# Sobel_FPGA_Block_1.net
KiCad netlist of a schematic drawn in Altium Designer
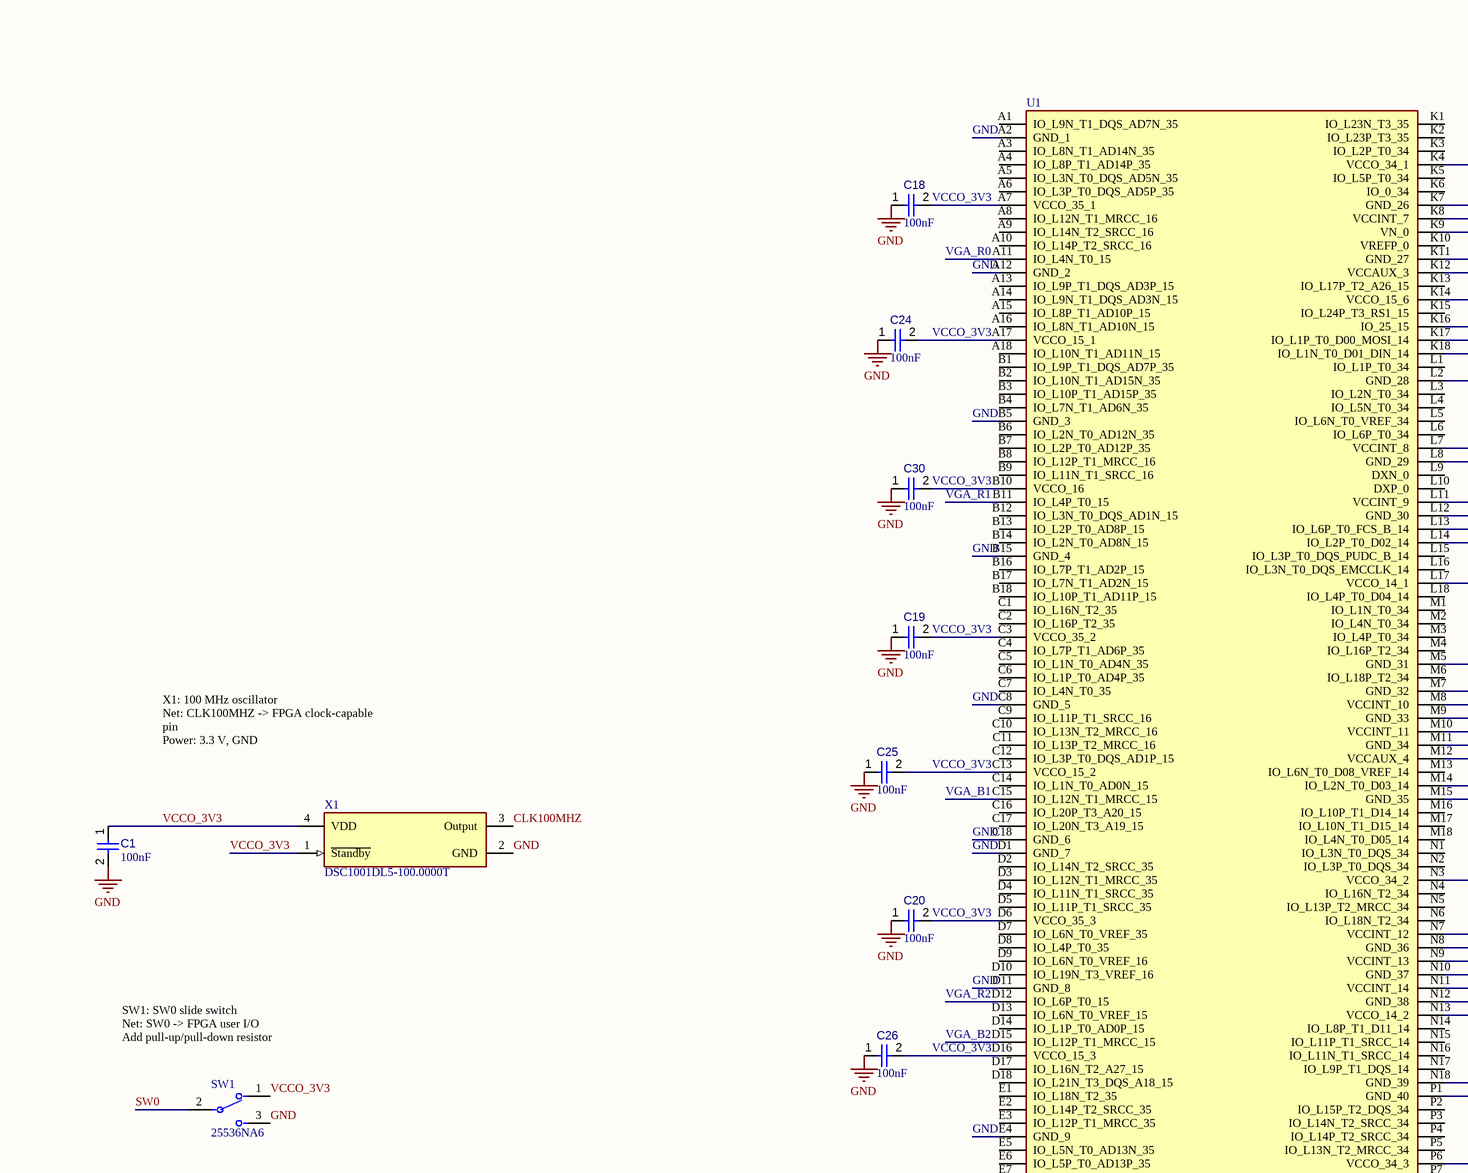
[diagram p0: Sobel_FPGA_Block (1).SchDoc, top left]
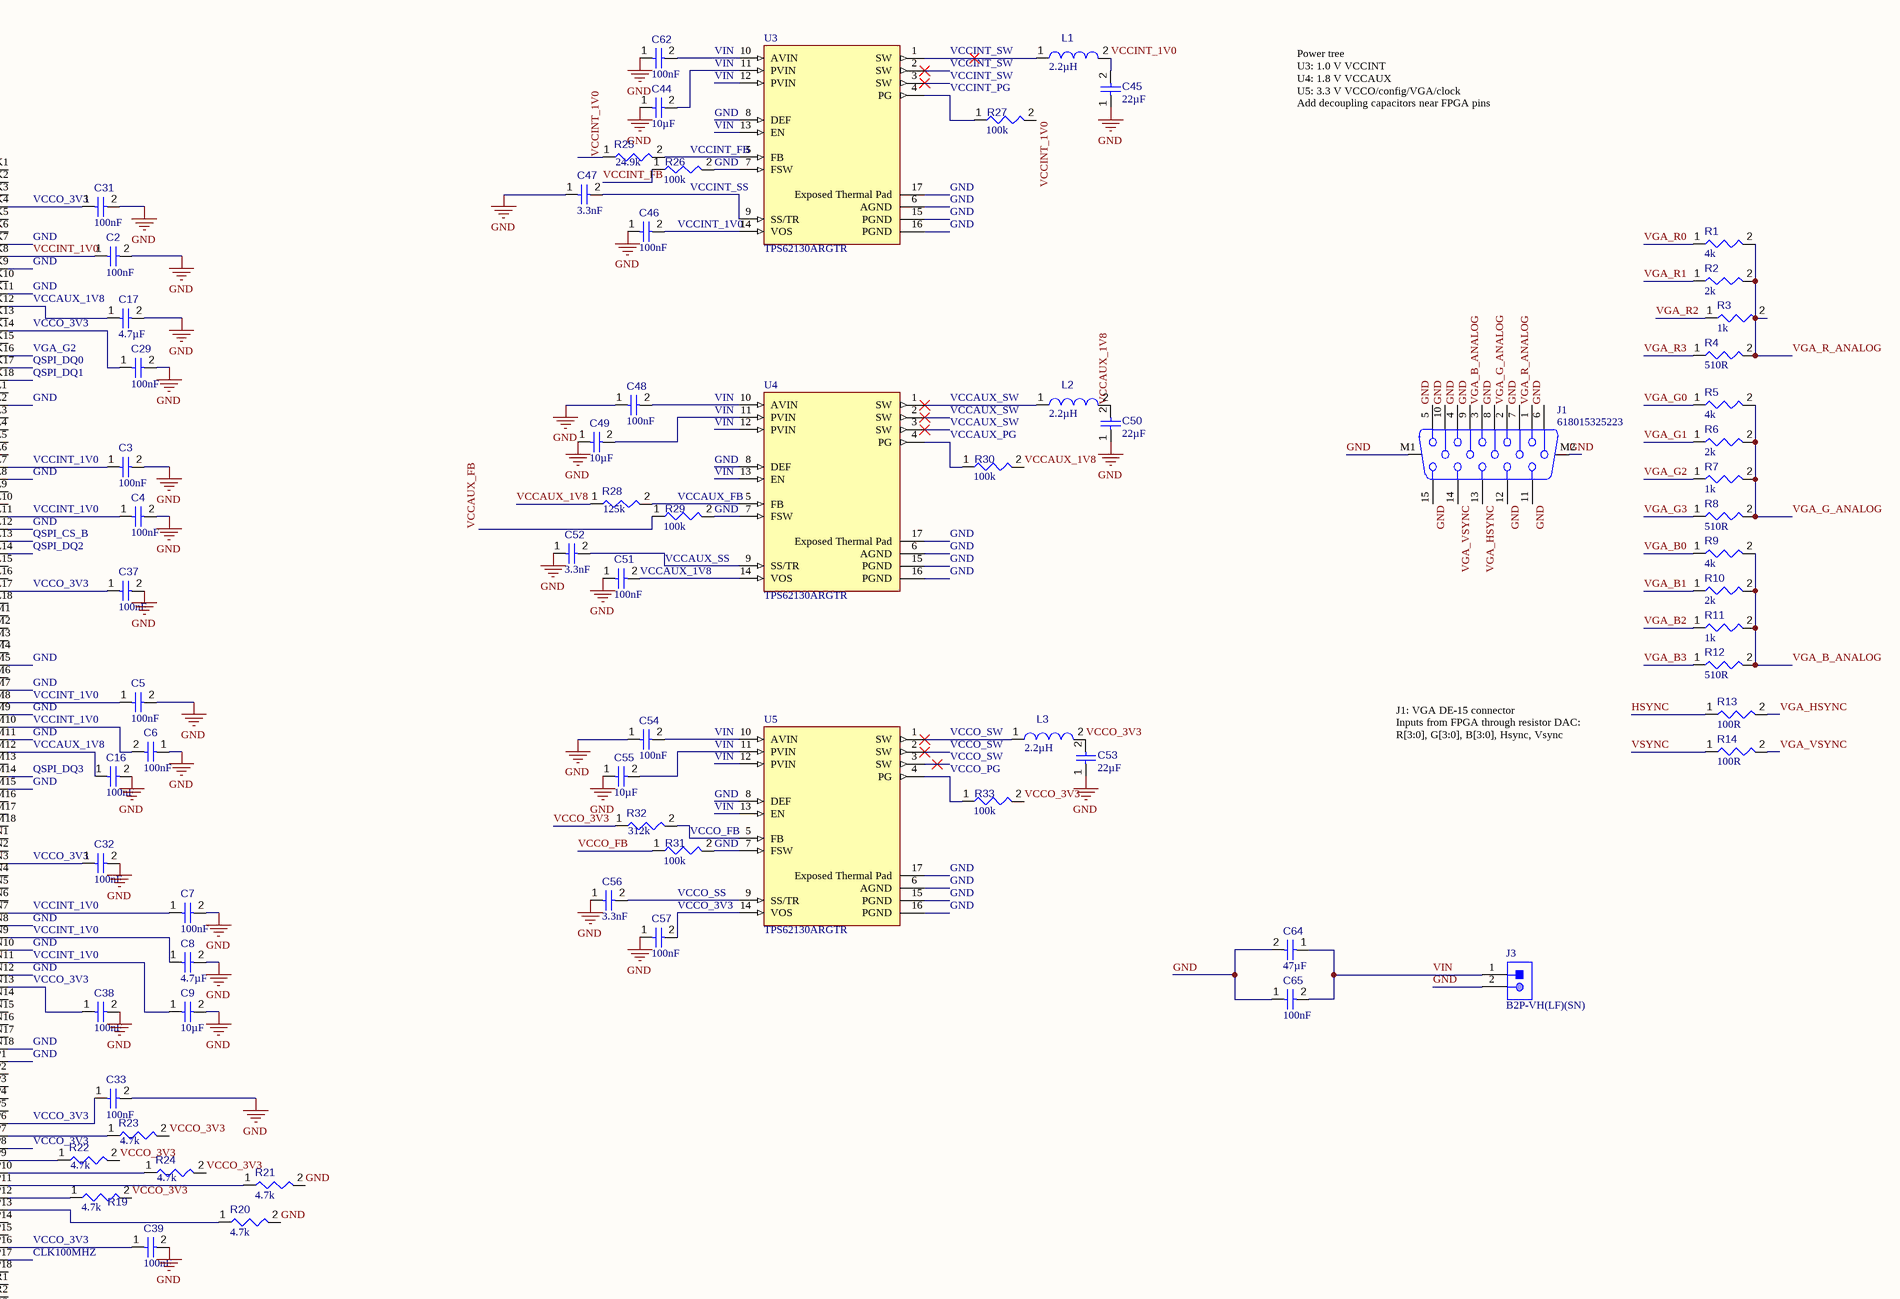
[diagram p1: Sobel_FPGA_Block (1).SchDoc, top right]
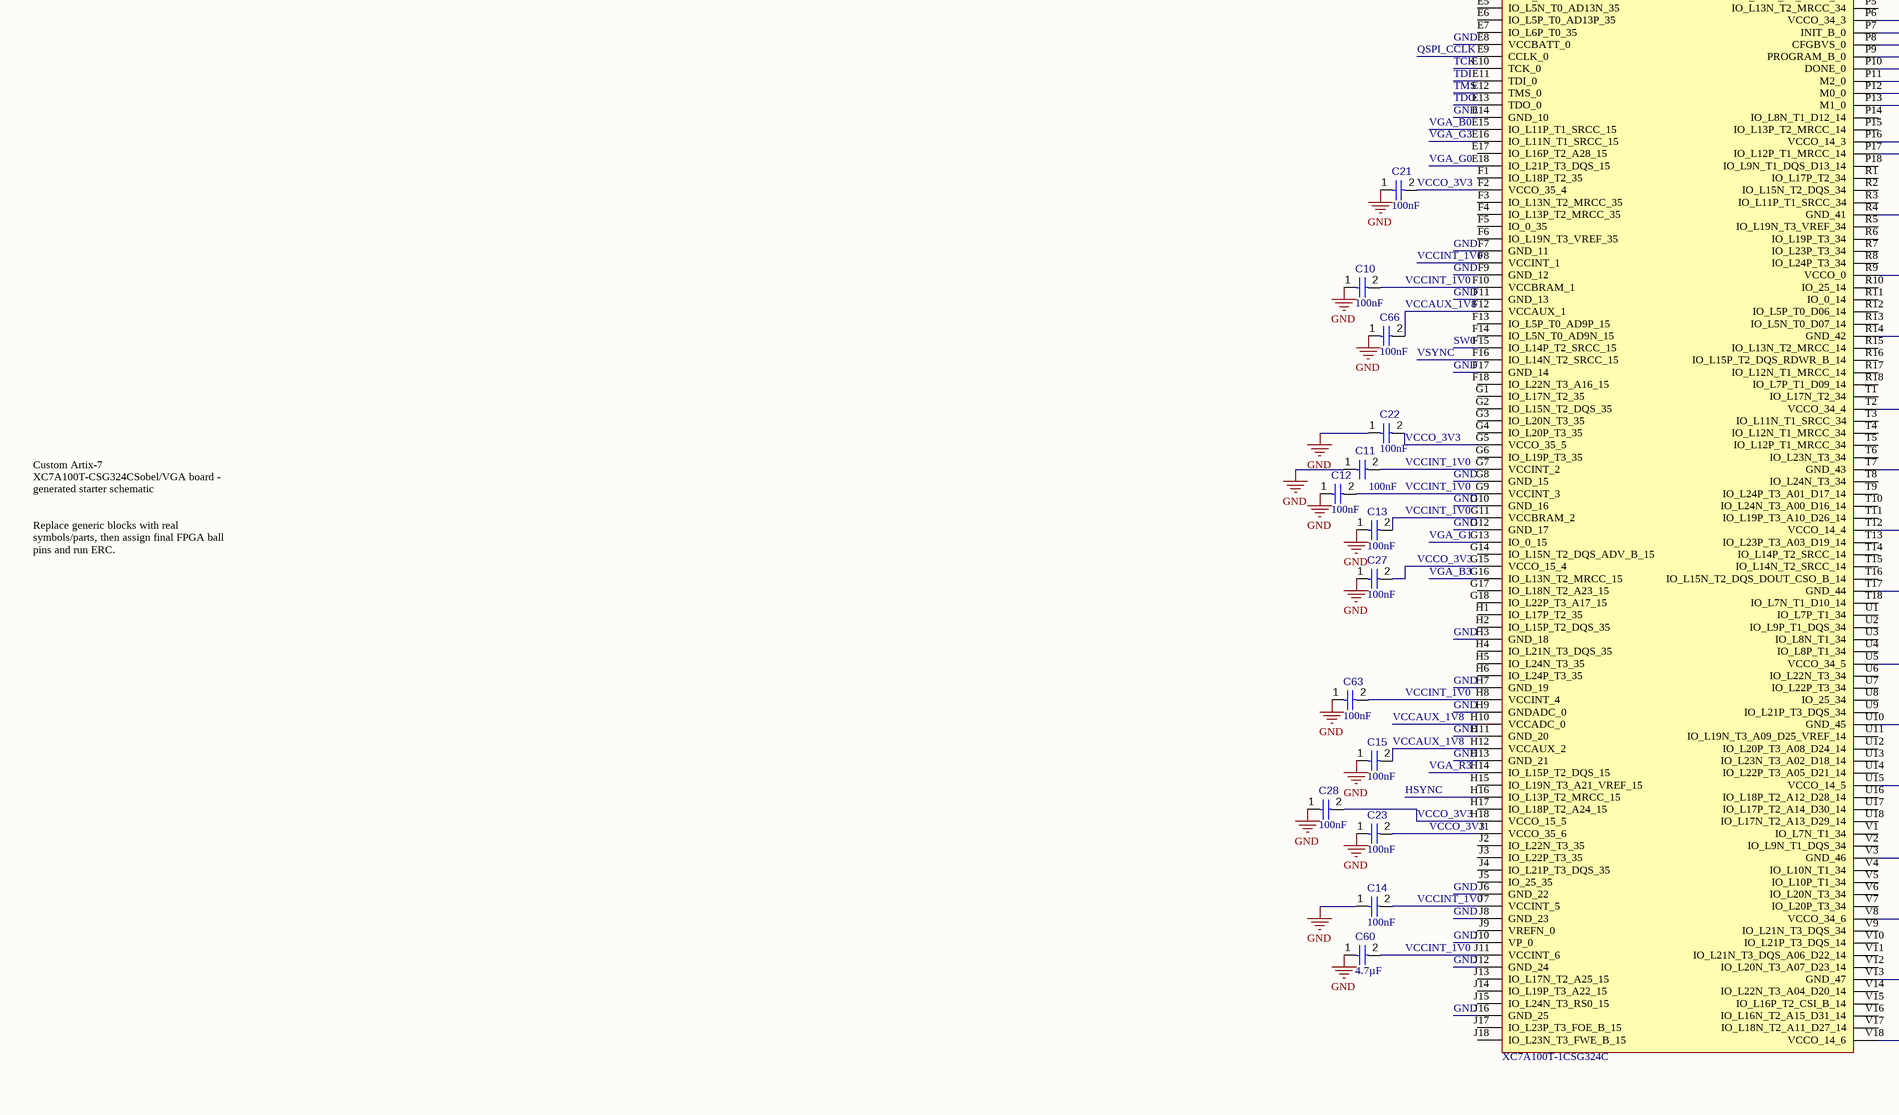
[diagram p2: Sobel_FPGA_Block (1).SchDoc, bottom left]
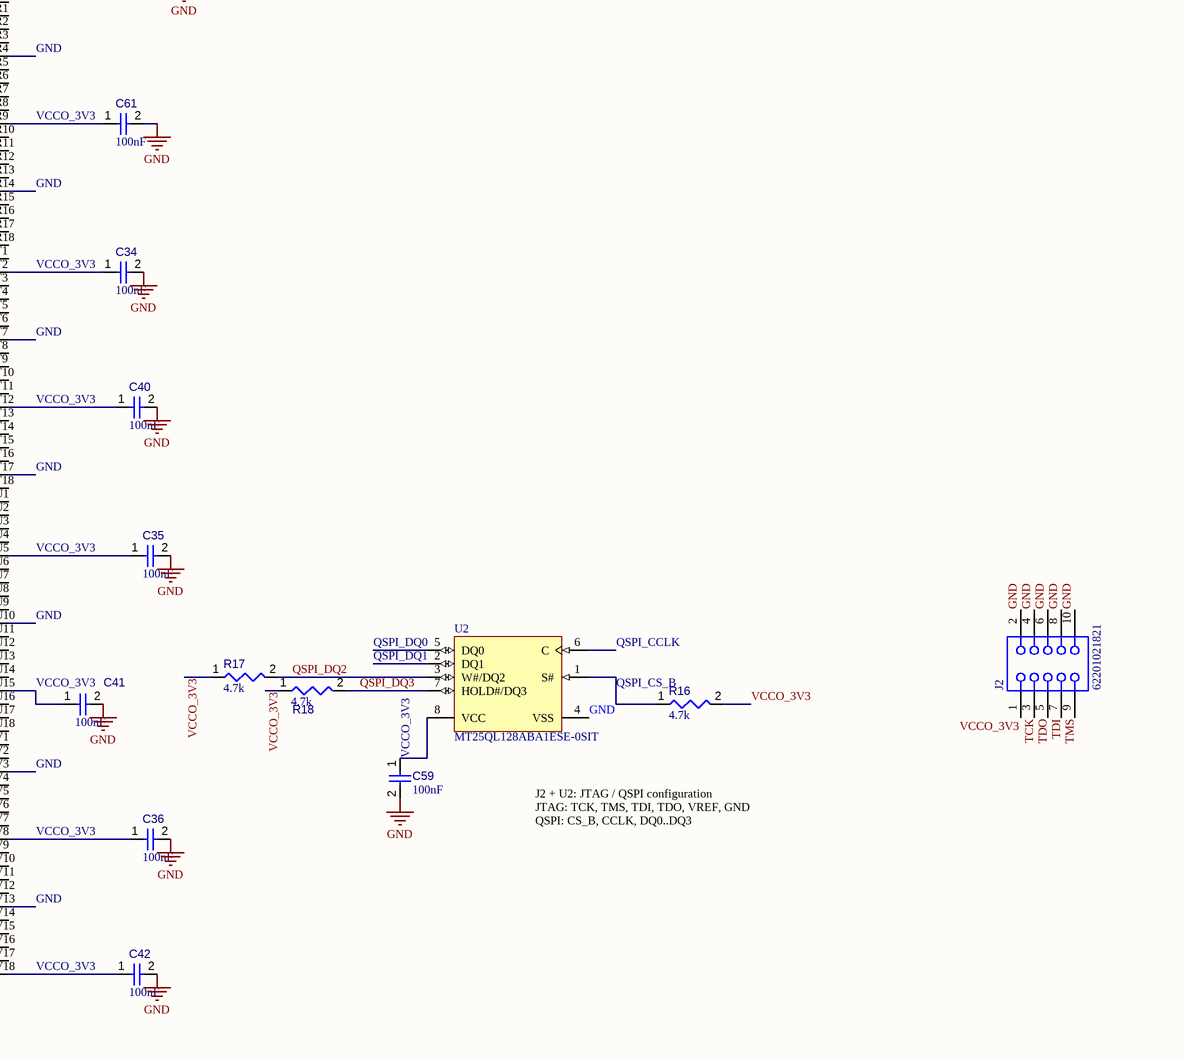
[diagram p3: Sobel_FPGA_Block (1).SchDoc, bottom right]

(export (version "E")
  (design (tool "Eeschema 10.0.6"))
  (components
    (comp (ref "C1")
      (value "100nF")
      (footprint "CAPC1005X56X25NL10T15")
      (description "Chip Capacitor, 6.8 nF, +/- 10%, 16 V, 0402 (1005 Metric)")
      (fields (field (name "TOLERANCE") "10%") (field (name "Comment") "Capacitor 6.8 nF +/- 10% 16 V 0402"))
      (libsource (lib "Turja Barua") (part "CAP-NP-2"))
    )
    (comp (ref "C2")
      (value "100nF")
      (footprint "CAPC1005X56X25NL10T15")
      (description "Chip Capacitor, 6.8 nF, +/- 10%, 16 V, 0402 (1005 Metric)")
      (fields (field (name "TOLERANCE") "10%") (field (name "Comment") "Capacitor 6.8 nF +/- 10% 16 V 0402"))
      (libsource (lib "Turja Barua") (part "CAP-NP-2"))
    )
    (comp (ref "C3")
      (value "100nF")
      (footprint "CAPC1005X56X25NL10T15")
      (description "Chip Capacitor, 6.8 nF, +/- 10%, 16 V, 0402 (1005 Metric)")
      (fields (field (name "TOLERANCE") "10%") (field (name "Comment") "Capacitor 6.8 nF +/- 10% 16 V 0402"))
      (libsource (lib "Turja Barua") (part "CAP-NP-2"))
    )
    (comp (ref "C4")
      (value "100nF")
      (footprint "CAPC1005X56X25NL10T15")
      (description "Chip Capacitor, 6.8 nF, +/- 10%, 16 V, 0402 (1005 Metric)")
      (fields (field (name "TOLERANCE") "10%") (field (name "Comment") "Capacitor 6.8 nF +/- 10% 16 V 0402"))
      (libsource (lib "Turja Barua") (part "CAP-NP-2"))
    )
    (comp (ref "C5")
      (value "100nF")
      (footprint "CAPC1005X56X25NL10T15")
      (description "Chip Capacitor, 6.8 nF, +/- 10%, 16 V, 0402 (1005 Metric)")
      (fields (field (name "TOLERANCE") "10%") (field (name "Comment") "Capacitor 6.8 nF +/- 10% 16 V 0402"))
      (libsource (lib "Turja Barua") (part "CAP-NP-2"))
    )
    (comp (ref "C6")
      (value "100nF")
      (footprint "CAPC1005X56X25NL10T15")
      (description "Chip Capacitor, 6.8 nF, +/- 10%, 16 V, 0402 (1005 Metric)")
      (fields (field (name "TOLERANCE") "10%") (field (name "Comment") "Capacitor 6.8 nF +/- 10% 16 V 0402"))
      (libsource (lib "Turja Barua") (part "CAP-NP-2"))
    )
    (comp (ref "C7")
      (value "100nF")
      (footprint "CAPC1005X56X25NL10T15")
      (description "Chip Capacitor, 6.8 nF, +/- 10%, 16 V, 0402 (1005 Metric)")
      (fields (field (name "TOLERANCE") "10%") (field (name "Comment") "Capacitor 6.8 nF +/- 10% 16 V 0402"))
      (libsource (lib "Turja Barua") (part "CAP-NP-2"))
    )
    (comp (ref "C8")
      (value "4.7µF")
      (footprint "CAPC3216X180X50NL20T25")
      (description "Chip Capacitor, 10 uF, +/- 10%, 16 V, 1206 (3216 Metric)")
      (fields (field (name "TOLERANCE") "10%") (field (name "Comment") "Capacitor 10 uF +/- 10% 16 V 1206"))
      (libsource (lib "Turja Barua") (part "CAP-NP-2"))
    )
    (comp (ref "C9")
      (value "10µF")
      (footprint "CAPC3216X180X50NL20T25")
      (description "Chip Capacitor, 10 uF, +/- 10%, 16 V, 1206 (3216 Metric)")
      (fields (field (name "TOLERANCE") "10%") (field (name "Comment") "Capacitor 10 uF +/- 10% 16 V 1206"))
      (libsource (lib "Turja Barua") (part "CAP-NP-2"))
    )
    (comp (ref "C10")
      (value "100nF")
      (footprint "CAPC1005X56X25NL10T15")
      (description "Chip Capacitor, 6.8 nF, +/- 10%, 16 V, 0402 (1005 Metric)")
      (fields (field (name "TOLERANCE") "10%") (field (name "Comment") "Capacitor 6.8 nF +/- 10% 16 V 0402"))
      (libsource (lib "Turja Barua") (part "CAP-NP-2"))
    )
    (comp (ref "C11")
      (value "100nF")
      (footprint "CAPC1005X56X25NL10T15")
      (description "Chip Capacitor, 6.8 nF, +/- 10%, 16 V, 0402 (1005 Metric)")
      (fields (field (name "TOLERANCE") "10%") (field (name "Comment") "Capacitor 6.8 nF +/- 10% 16 V 0402"))
      (libsource (lib "Turja Barua") (part "CAP-NP-2"))
    )
    (comp (ref "C12")
      (value "100nF")
      (footprint "CAPC1005X56X25NL10T15")
      (description "Chip Capacitor, 6.8 nF, +/- 10%, 16 V, 0402 (1005 Metric)")
      (fields (field (name "TOLERANCE") "10%") (field (name "Comment") "Capacitor 6.8 nF +/- 10% 16 V 0402"))
      (libsource (lib "Turja Barua") (part "CAP-NP-2"))
    )
    (comp (ref "C13")
      (value "100nF")
      (footprint "CAPC1005X56X25NL10T15")
      (description "Chip Capacitor, 6.8 nF, +/- 10%, 16 V, 0402 (1005 Metric)")
      (fields (field (name "TOLERANCE") "10%") (field (name "Comment") "Capacitor 6.8 nF +/- 10% 16 V 0402"))
      (libsource (lib "Turja Barua") (part "CAP-NP-2"))
    )
    (comp (ref "C14")
      (value "100nF")
      (footprint "CAPC1005X56X25NL10T15")
      (description "Chip Capacitor, 6.8 nF, +/- 10%, 16 V, 0402 (1005 Metric)")
      (fields (field (name "TOLERANCE") "10%") (field (name "Comment") "Capacitor 6.8 nF +/- 10% 16 V 0402"))
      (libsource (lib "Turja Barua") (part "CAP-NP-2"))
    )
    (comp (ref "C15")
      (value "100nF")
      (footprint "CAPC1005X56X25NL10T15")
      (description "Chip Capacitor, 6.8 nF, +/- 10%, 16 V, 0402 (1005 Metric)")
      (fields (field (name "TOLERANCE") "10%") (field (name "Comment") "Capacitor 6.8 nF +/- 10% 16 V 0402"))
      (libsource (lib "Turja Barua") (part "CAP-NP-2"))
    )
    (comp (ref "C16")
      (value "100nF")
      (footprint "CAPC1005X56X25NL10T15")
      (description "Chip Capacitor, 6.8 nF, +/- 10%, 16 V, 0402 (1005 Metric)")
      (fields (field (name "TOLERANCE") "10%") (field (name "Comment") "Capacitor 6.8 nF +/- 10% 16 V 0402"))
      (libsource (lib "Turja Barua") (part "CAP-NP-2"))
    )
    (comp (ref "C17")
      (value "4.7µF")
      (footprint "CAPC3216X180X50NL20T25")
      (description "Chip Capacitor, 10 uF, +/- 10%, 16 V, 1206 (3216 Metric)")
      (fields (field (name "TOLERANCE") "10%") (field (name "Comment") "Capacitor 10 uF +/- 10% 16 V 1206"))
      (libsource (lib "Turja Barua") (part "CAP-NP-2"))
    )
    (comp (ref "C18")
      (value "100nF")
      (footprint "CAPC1005X56X25NL10T15")
      (description "Chip Capacitor, 6.8 nF, +/- 10%, 16 V, 0402 (1005 Metric)")
      (fields (field (name "TOLERANCE") "10%") (field (name "Comment") "Capacitor 6.8 nF +/- 10% 16 V 0402"))
      (libsource (lib "Turja Barua") (part "CAP-NP-2"))
    )
    (comp (ref "C19")
      (value "100nF")
      (footprint "CAPC1005X56X25NL10T15")
      (description "Chip Capacitor, 6.8 nF, +/- 10%, 16 V, 0402 (1005 Metric)")
      (fields (field (name "TOLERANCE") "10%") (field (name "Comment") "Capacitor 6.8 nF +/- 10% 16 V 0402"))
      (libsource (lib "Turja Barua") (part "CAP-NP-2"))
    )
    (comp (ref "C20")
      (value "100nF")
      (footprint "CAPC1005X56X25NL10T15")
      (description "Chip Capacitor, 6.8 nF, +/- 10%, 16 V, 0402 (1005 Metric)")
      (fields (field (name "TOLERANCE") "10%") (field (name "Comment") "Capacitor 6.8 nF +/- 10% 16 V 0402"))
      (libsource (lib "Turja Barua") (part "CAP-NP-2"))
    )
    (comp (ref "C21")
      (value "100nF")
      (footprint "CAPC1005X56X25NL10T15")
      (description "Chip Capacitor, 6.8 nF, +/- 10%, 16 V, 0402 (1005 Metric)")
      (fields (field (name "TOLERANCE") "10%") (field (name "Comment") "Capacitor 6.8 nF +/- 10% 16 V 0402"))
      (libsource (lib "Turja Barua") (part "CAP-NP-2"))
    )
    (comp (ref "C22")
      (value "100nF")
      (footprint "CAPC1005X56X25NL10T15")
      (description "Chip Capacitor, 6.8 nF, +/- 10%, 16 V, 0402 (1005 Metric)")
      (fields (field (name "TOLERANCE") "10%") (field (name "Comment") "Capacitor 6.8 nF +/- 10% 16 V 0402"))
      (libsource (lib "Turja Barua") (part "CAP-NP-2"))
    )
    (comp (ref "C23")
      (value "100nF")
      (footprint "CAPC1005X56X25NL10T15")
      (description "Chip Capacitor, 6.8 nF, +/- 10%, 16 V, 0402 (1005 Metric)")
      (fields (field (name "TOLERANCE") "10%") (field (name "Comment") "Capacitor 6.8 nF +/- 10% 16 V 0402"))
      (libsource (lib "Turja Barua") (part "CAP-NP-2"))
    )
    (comp (ref "C24")
      (value "100nF")
      (footprint "CAPC1005X56X25NL10T15")
      (description "Chip Capacitor, 6.8 nF, +/- 10%, 16 V, 0402 (1005 Metric)")
      (fields (field (name "TOLERANCE") "10%") (field (name "Comment") "Capacitor 6.8 nF +/- 10% 16 V 0402"))
      (libsource (lib "Turja Barua") (part "CAP-NP-2"))
    )
    (comp (ref "C25")
      (value "100nF")
      (footprint "CAPC1005X56X25NL10T15")
      (description "Chip Capacitor, 6.8 nF, +/- 10%, 16 V, 0402 (1005 Metric)")
      (fields (field (name "TOLERANCE") "10%") (field (name "Comment") "Capacitor 6.8 nF +/- 10% 16 V 0402"))
      (libsource (lib "Turja Barua") (part "CAP-NP-2"))
    )
    (comp (ref "C26")
      (value "100nF")
      (footprint "CAPC1005X56X25NL10T15")
      (description "Chip Capacitor, 6.8 nF, +/- 10%, 16 V, 0402 (1005 Metric)")
      (fields (field (name "TOLERANCE") "10%") (field (name "Comment") "Capacitor 6.8 nF +/- 10% 16 V 0402"))
      (libsource (lib "Turja Barua") (part "CAP-NP-2"))
    )
    (comp (ref "C27")
      (value "100nF")
      (footprint "CAPC1005X56X25NL10T15")
      (description "Chip Capacitor, 6.8 nF, +/- 10%, 16 V, 0402 (1005 Metric)")
      (fields (field (name "TOLERANCE") "10%") (field (name "Comment") "Capacitor 6.8 nF +/- 10% 16 V 0402"))
      (libsource (lib "Turja Barua") (part "CAP-NP-2"))
    )
    (comp (ref "C28")
      (value "100nF")
      (footprint "CAPC1005X56X25NL10T15")
      (description "Chip Capacitor, 6.8 nF, +/- 10%, 16 V, 0402 (1005 Metric)")
      (fields (field (name "TOLERANCE") "10%") (field (name "Comment") "Capacitor 6.8 nF +/- 10% 16 V 0402"))
      (libsource (lib "Turja Barua") (part "CAP-NP-2"))
    )
    (comp (ref "C29")
      (value "100nF")
      (footprint "CAPC1005X56X25NL10T15")
      (description "Chip Capacitor, 6.8 nF, +/- 10%, 16 V, 0402 (1005 Metric)")
      (fields (field (name "TOLERANCE") "10%") (field (name "Comment") "Capacitor 6.8 nF +/- 10% 16 V 0402"))
      (libsource (lib "Turja Barua") (part "CAP-NP-2"))
    )
    (comp (ref "C30")
      (value "100nF")
      (footprint "CAPC1005X56X25NL10T15")
      (description "Chip Capacitor, 6.8 nF, +/- 10%, 16 V, 0402 (1005 Metric)")
      (fields (field (name "TOLERANCE") "10%") (field (name "Comment") "Capacitor 6.8 nF +/- 10% 16 V 0402"))
      (libsource (lib "Turja Barua") (part "CAP-NP-2"))
    )
    (comp (ref "C31")
      (value "100nF")
      (footprint "CAPC1005X56X25NL10T15")
      (description "Chip Capacitor, 6.8 nF, +/- 10%, 16 V, 0402 (1005 Metric)")
      (fields (field (name "TOLERANCE") "10%") (field (name "Comment") "Capacitor 6.8 nF +/- 10% 16 V 0402"))
      (libsource (lib "Turja Barua") (part "CAP-NP-2"))
    )
    (comp (ref "C32")
      (value "100nF")
      (footprint "CAPC1005X56X25NL10T15")
      (description "Chip Capacitor, 6.8 nF, +/- 10%, 16 V, 0402 (1005 Metric)")
      (fields (field (name "TOLERANCE") "10%") (field (name "Comment") "Capacitor 6.8 nF +/- 10% 16 V 0402"))
      (libsource (lib "Turja Barua") (part "CAP-NP-2"))
    )
    (comp (ref "C33")
      (value "100nF")
      (footprint "CAPC1005X56X25NL10T15")
      (description "Chip Capacitor, 6.8 nF, +/- 10%, 16 V, 0402 (1005 Metric)")
      (fields (field (name "TOLERANCE") "10%") (field (name "Comment") "Capacitor 6.8 nF +/- 10% 16 V 0402"))
      (libsource (lib "Turja Barua") (part "CAP-NP-2"))
    )
    (comp (ref "C34")
      (value "100nF")
      (footprint "CAPC1005X56X25NL10T15")
      (description "Chip Capacitor, 6.8 nF, +/- 10%, 16 V, 0402 (1005 Metric)")
      (fields (field (name "TOLERANCE") "10%") (field (name "Comment") "Capacitor 6.8 nF +/- 10% 16 V 0402"))
      (libsource (lib "Turja Barua") (part "CAP-NP-2"))
    )
    (comp (ref "C35")
      (value "100nF")
      (footprint "CAPC1005X56X25NL10T15")
      (description "Chip Capacitor, 6.8 nF, +/- 10%, 16 V, 0402 (1005 Metric)")
      (fields (field (name "TOLERANCE") "10%") (field (name "Comment") "Capacitor 6.8 nF +/- 10% 16 V 0402"))
      (libsource (lib "Turja Barua") (part "CAP-NP-2"))
    )
    (comp (ref "C36")
      (value "100nF")
      (footprint "CAPC1005X56X25NL10T15")
      (description "Chip Capacitor, 6.8 nF, +/- 10%, 16 V, 0402 (1005 Metric)")
      (fields (field (name "TOLERANCE") "10%") (field (name "Comment") "Capacitor 6.8 nF +/- 10% 16 V 0402"))
      (libsource (lib "Turja Barua") (part "CAP-NP-2"))
    )
    (comp (ref "C37")
      (value "100nF")
      (footprint "CAPC1005X56X25NL10T15")
      (description "Chip Capacitor, 6.8 nF, +/- 10%, 16 V, 0402 (1005 Metric)")
      (fields (field (name "TOLERANCE") "10%") (field (name "Comment") "Capacitor 6.8 nF +/- 10% 16 V 0402"))
      (libsource (lib "Turja Barua") (part "CAP-NP-2"))
    )
    (comp (ref "C38")
      (value "100nF")
      (footprint "CAPC1005X56X25NL10T15")
      (description "Chip Capacitor, 6.8 nF, +/- 10%, 16 V, 0402 (1005 Metric)")
      (fields (field (name "TOLERANCE") "10%") (field (name "Comment") "Capacitor 6.8 nF +/- 10% 16 V 0402"))
      (libsource (lib "Turja Barua") (part "CAP-NP-2"))
    )
    (comp (ref "C39")
      (value "100nF")
      (footprint "CAPC1005X56X25NL10T15")
      (description "Chip Capacitor, 6.8 nF, +/- 10%, 16 V, 0402 (1005 Metric)")
      (fields (field (name "TOLERANCE") "10%") (field (name "Comment") "Capacitor 6.8 nF +/- 10% 16 V 0402"))
      (libsource (lib "Turja Barua") (part "CAP-NP-2"))
    )
    (comp (ref "C40")
      (value "100nF")
      (footprint "CAPC1005X56X25NL10T15")
      (description "Chip Capacitor, 6.8 nF, +/- 10%, 16 V, 0402 (1005 Metric)")
      (fields (field (name "TOLERANCE") "10%") (field (name "Comment") "Capacitor 6.8 nF +/- 10% 16 V 0402"))
      (libsource (lib "Turja Barua") (part "CAP-NP-2"))
    )
    (comp (ref "C41")
      (value "100nF")
      (footprint "CAPC1005X56X25NL10T15")
      (description "Chip Capacitor, 6.8 nF, +/- 10%, 16 V, 0402 (1005 Metric)")
      (fields (field (name "TOLERANCE") "10%") (field (name "Comment") "Capacitor 6.8 nF +/- 10% 16 V 0402"))
      (libsource (lib "Turja Barua") (part "CAP-NP-2"))
    )
    (comp (ref "C42")
      (value "100nF")
      (footprint "CAPC1005X56X25NL10T15")
      (description "Chip Capacitor, 6.8 nF, +/- 10%, 16 V, 0402 (1005 Metric)")
      (fields (field (name "TOLERANCE") "10%") (field (name "Comment") "Capacitor 6.8 nF +/- 10% 16 V 0402"))
      (libsource (lib "Turja Barua") (part "CAP-NP-2"))
    )
    (comp (ref "C44")
      (value "10µF")
      (footprint "CAPC3216X180X50NL20T25")
      (description "Chip Capacitor, 10 uF, +/- 10%, 16 V, 1206 (3216 Metric)")
      (fields (field (name "TOLERANCE") "10%") (field (name "Comment") "Capacitor 10 uF +/- 10% 16 V 1206"))
      (libsource (lib "Turja Barua") (part "CAP-NP-2"))
    )
    (comp (ref "C45")
      (value "22µF")
      (footprint "CAPC3216X180X50NL20T25")
      (description "Chip Capacitor, 10 uF, +/- 10%, 16 V, 1206 (3216 Metric)")
      (fields (field (name "TOLERANCE") "10%") (field (name "Comment") "Capacitor 10 uF +/- 10% 16 V 1206"))
      (libsource (lib "Turja Barua") (part "CAP-NP-2"))
    )
    (comp (ref "C46")
      (value "100nF")
      (footprint "CAPC1005X56X25NL10T15")
      (description "Chip Capacitor, 6.8 nF, +/- 10%, 16 V, 0402 (1005 Metric)")
      (fields (field (name "TOLERANCE") "10%") (field (name "Comment") "Capacitor 6.8 nF +/- 10% 16 V 0402"))
      (libsource (lib "Turja Barua") (part "CAP-NP-2"))
    )
    (comp (ref "C47")
      (value "3.3nF")
      (footprint "CAPC1005X56X25NL10T15")
      (description "Chip Capacitor, 6.8 nF, +/- 10%, 16 V, 0402 (1005 Metric)")
      (fields (field (name "TOLERANCE") "10%") (field (name "Comment") "Capacitor 6.8 nF +/- 10% 16 V 0402"))
      (libsource (lib "Turja Barua") (part "CAP-NP-2"))
    )
    (comp (ref "C48")
      (value "100nF")
      (footprint "CAPC1005X56X25NL10T15")
      (description "Chip Capacitor, 6.8 nF, +/- 10%, 16 V, 0402 (1005 Metric)")
      (fields (field (name "TOLERANCE") "10%") (field (name "Comment") "Capacitor 6.8 nF +/- 10% 16 V 0402"))
      (libsource (lib "Turja Barua") (part "CAP-NP-2"))
    )
    (comp (ref "C49")
      (value "10µF")
      (footprint "CAPC3216X180X50NL20T25")
      (description "Chip Capacitor, 10 uF, +/- 10%, 16 V, 1206 (3216 Metric)")
      (fields (field (name "TOLERANCE") "10%") (field (name "Comment") "Capacitor 10 uF +/- 10% 16 V 1206"))
      (libsource (lib "Turja Barua") (part "CAP-NP-2"))
    )
    (comp (ref "C50")
      (value "22µF")
      (footprint "CAPC3216X180X50NL20T25")
      (description "Chip Capacitor, 10 uF, +/- 10%, 16 V, 1206 (3216 Metric)")
      (fields (field (name "TOLERANCE") "10%") (field (name "Comment") "Capacitor 10 uF +/- 10% 16 V 1206"))
      (libsource (lib "Turja Barua") (part "CAP-NP-2"))
    )
    (comp (ref "C51")
      (value "100nF")
      (footprint "CAPC1005X56X25NL10T15")
      (description "Chip Capacitor, 6.8 nF, +/- 10%, 16 V, 0402 (1005 Metric)")
      (fields (field (name "TOLERANCE") "10%") (field (name "Comment") "Capacitor 6.8 nF +/- 10% 16 V 0402"))
      (libsource (lib "Turja Barua") (part "CAP-NP-2"))
    )
    (comp (ref "C52")
      (value "3.3nF")
      (footprint "CAPC1005X56X25NL10T15")
      (description "Chip Capacitor, 6.8 nF, +/- 10%, 16 V, 0402 (1005 Metric)")
      (fields (field (name "TOLERANCE") "10%") (field (name "Comment") "Capacitor 6.8 nF +/- 10% 16 V 0402"))
      (libsource (lib "Turja Barua") (part "CAP-NP-2"))
    )
    (comp (ref "C53")
      (value "22µF")
      (footprint "CAPC3216X180X50NL20T25")
      (description "Chip Capacitor, 10 uF, +/- 10%, 16 V, 1206 (3216 Metric)")
      (fields (field (name "TOLERANCE") "10%") (field (name "Comment") "Capacitor 10 uF +/- 10% 16 V 1206"))
      (libsource (lib "Turja Barua") (part "CAP-NP-2"))
    )
    (comp (ref "C54")
      (value "100nF")
      (footprint "CAPC1005X56X25NL10T15")
      (description "Chip Capacitor, 6.8 nF, +/- 10%, 16 V, 0402 (1005 Metric)")
      (fields (field (name "TOLERANCE") "10%") (field (name "Comment") "Capacitor 6.8 nF +/- 10% 16 V 0402"))
      (libsource (lib "Turja Barua") (part "CAP-NP-2"))
    )
    (comp (ref "C55")
      (value "10µF")
      (footprint "CAPC3216X180X50NL20T25")
      (description "Chip Capacitor, 10 uF, +/- 10%, 16 V, 1206 (3216 Metric)")
      (fields (field (name "TOLERANCE") "10%") (field (name "Comment") "Capacitor 10 uF +/- 10% 16 V 1206"))
      (libsource (lib "Turja Barua") (part "CAP-NP-2"))
    )
    (comp (ref "C56")
      (value "3.3nF")
      (footprint "CAPC1005X56X25NL10T15")
      (description "Chip Capacitor, 6.8 nF, +/- 10%, 16 V, 0402 (1005 Metric)")
      (fields (field (name "TOLERANCE") "10%") (field (name "Comment") "Capacitor 6.8 nF +/- 10% 16 V 0402"))
      (libsource (lib "Turja Barua") (part "CAP-NP-2"))
    )
    (comp (ref "C57")
      (value "100nF")
      (footprint "CAPC1005X56X25NL10T15")
      (description "Chip Capacitor, 6.8 nF, +/- 10%, 16 V, 0402 (1005 Metric)")
      (fields (field (name "TOLERANCE") "10%") (field (name "Comment") "Capacitor 6.8 nF +/- 10% 16 V 0402"))
      (libsource (lib "Turja Barua") (part "CAP-NP-2"))
    )
    (comp (ref "C59")
      (value "100nF")
      (footprint "CAPC1005X56X25NL10T15")
      (description "Chip Capacitor, 6.8 nF, +/- 10%, 16 V, 0402 (1005 Metric)")
      (fields (field (name "TOLERANCE") "10%") (field (name "Comment") "Capacitor 6.8 nF +/- 10% 16 V 0402"))
      (libsource (lib "Turja Barua") (part "CAP-NP-2"))
    )
    (comp (ref "C60")
      (value "4.7µF")
      (footprint "CAPC3216X180X50NL20T25")
      (description "Chip Capacitor, 10 uF, +/- 10%, 16 V, 1206 (3216 Metric)")
      (fields (field (name "TOLERANCE") "10%") (field (name "Comment") "Capacitor 10 uF +/- 10% 16 V 1206"))
      (libsource (lib "Turja Barua") (part "CAP-NP-2"))
    )
    (comp (ref "C61")
      (value "100nF")
      (footprint "CAPC1005X56X25NL10T15")
      (description "Chip Capacitor, 6.8 nF, +/- 10%, 16 V, 0402 (1005 Metric)")
      (fields (field (name "TOLERANCE") "10%") (field (name "Comment") "Capacitor 6.8 nF +/- 10% 16 V 0402"))
      (libsource (lib "Turja Barua") (part "CAP-NP-2"))
    )
    (comp (ref "C62")
      (value "100nF")
      (footprint "CAPC1005X56X25NL10T15")
      (description "Chip Capacitor, 6.8 nF, +/- 10%, 16 V, 0402 (1005 Metric)")
      (fields (field (name "TOLERANCE") "10%") (field (name "Comment") "Capacitor 6.8 nF +/- 10% 16 V 0402"))
      (libsource (lib "Turja Barua") (part "CAP-NP-2"))
    )
    (comp (ref "C63")
      (value "100nF")
      (footprint "CAPC1005X56X25NL10T15")
      (description "Chip Capacitor, 6.8 nF, +/- 10%, 16 V, 0402 (1005 Metric)")
      (fields (field (name "TOLERANCE") "10%") (field (name "Comment") "Capacitor 6.8 nF +/- 10% 16 V 0402"))
      (libsource (lib "Turja Barua") (part "CAP-NP-2"))
    )
    (comp (ref "C64")
      (value "47µF")
      (footprint "CAPC3216X180X50NL20T25")
      (description "Chip Capacitor, 10 uF, +/- 10%, 16 V, 1206 (3216 Metric)")
      (fields (field (name "TOLERANCE") "10%") (field (name "Comment") "Capacitor 10 uF +/- 10% 16 V 1206"))
      (libsource (lib "Turja Barua") (part "CAP-NP-2"))
    )
    (comp (ref "C65")
      (value "100nF")
      (footprint "CAPC1005X56X25NL10T15")
      (description "Chip Capacitor, 6.8 nF, +/- 10%, 16 V, 0402 (1005 Metric)")
      (fields (field (name "TOLERANCE") "10%") (field (name "Comment") "Capacitor 6.8 nF +/- 10% 16 V 0402"))
      (libsource (lib "Turja Barua") (part "CAP-NP-2"))
    )
    (comp (ref "C66")
      (value "100nF")
      (footprint "CAPC1005X56X25NL10T15")
      (description "Chip Capacitor, 6.8 nF, +/- 10%, 16 V, 0402 (1005 Metric)")
      (fields (field (name "TOLERANCE") "10%") (field (name "Comment") "Capacitor 6.8 nF +/- 10% 16 V 0402"))
      (libsource (lib "Turja Barua") (part "CAP-NP-2"))
    )
    (comp (ref "J1")
      (value "618015325223")
      (footprint "618015325223")
      (description "Hd-D Sub Conn, R/A Rcpt, 15Pos, De, Tht Rohs Compliant: Yes")
      (libsource (lib "Turja Barua") (part "D-Sub_Female_15p_High Density"))
    )
    (comp (ref "J2")
      (value "62201021821")
      (footprint "62201021821")
      (description "Connector Header Surface Mount 10 position 0.050\" (1.27mm)-JTAG Connector")
      (libsource (lib "Turja Barua") (part "Header_Female_2R_10P"))
    )
    (comp (ref "J3")
      (value "B2P-VH(LF)(SN)")
      (footprint "JST-B2P-VH(LF)(SN)_V")
      (fields (field (name "MANUFACTURER") "JST"))
      (libsource (lib "Turja Barua") (part "CN-1P-M-R2"))
    )
    (comp (ref "L1")
      (value "2.2µH")
      (footprint "SUSUMU-PCMB063T_V")
      (description "Shielded Wirewound Inductor, 2.2 uH, +/- 20%, -20 to 120 degC, 2-Pin SMD, RoHS, Tape and Reel")
      (fields (field (name "TOLERANCE") "20%") (field (name "Comment") "PCMB063T-2R2MS"))
      (libsource (lib "Turja Barua") (part "CMP-001-0020-1"))
    )
    (comp (ref "L2")
      (value "2.2µH")
      (footprint "SUSUMU-PCMB063T_V")
      (description "Shielded Wirewound Inductor, 2.2 uH, +/- 20%, -20 to 120 degC, 2-Pin SMD, RoHS, Tape and Reel")
      (fields (field (name "TOLERANCE") "20%") (field (name "Comment") "PCMB063T-2R2MS"))
      (libsource (lib "Turja Barua") (part "CMP-001-0020-1"))
    )
    (comp (ref "L3")
      (value "2.2µH")
      (footprint "SUSUMU-PCMB063T_V")
      (description "Shielded Wirewound Inductor, 2.2 uH, +/- 20%, -20 to 120 degC, 2-Pin SMD, RoHS, Tape and Reel")
      (fields (field (name "TOLERANCE") "20%") (field (name "Comment") "PCMB063T-2R2MS"))
      (libsource (lib "Turja Barua") (part "CMP-001-0020-1"))
    )
    (comp (ref "R1")
      (value "4k")
      (footprint "RESA60-630X240")
      (description "Axial Resistor, 475 Ohm, +/- 1%, 0.25 W, -55 to 155 degC, 2-Pin THD, RoHS, Bulk")
      (fields (field (name "MANUFACTURER") "Yageo") (field (name "TOLERANCE") "1%"))
      (libsource (lib "Turja Barua") (part "RES-2"))
    )
    (comp (ref "R2")
      (value "2k")
      (footprint "RESA60-630X240")
      (description "Axial Resistor, 475 Ohm, +/- 1%, 0.25 W, -55 to 155 degC, 2-Pin THD, RoHS, Bulk")
      (fields (field (name "MANUFACTURER") "Yageo") (field (name "TOLERANCE") "1%"))
      (libsource (lib "Turja Barua") (part "RES-2"))
    )
    (comp (ref "R3")
      (value "1k")
      (footprint "RESA60-630X240")
      (description "Axial Resistor, 475 Ohm, +/- 1%, 0.25 W, -55 to 155 degC, 2-Pin THD, RoHS, Bulk")
      (fields (field (name "MANUFACTURER") "Yageo") (field (name "TOLERANCE") "1%"))
      (libsource (lib "Turja Barua") (part "RES-2"))
    )
    (comp (ref "R4")
      (value "510R")
      (footprint "RESA60-630X240")
      (description "Axial Resistor, 475 Ohm, +/- 1%, 0.25 W, -55 to 155 degC, 2-Pin THD, RoHS, Bulk")
      (fields (field (name "MANUFACTURER") "Yageo") (field (name "TOLERANCE") "1%"))
      (libsource (lib "Turja Barua") (part "RES-2"))
    )
    (comp (ref "R5")
      (value "4k")
      (footprint "RESA60-630X240")
      (description "Axial Resistor, 475 Ohm, +/- 1%, 0.25 W, -55 to 155 degC, 2-Pin THD, RoHS, Bulk")
      (fields (field (name "MANUFACTURER") "Yageo") (field (name "TOLERANCE") "1%"))
      (libsource (lib "Turja Barua") (part "RES-2"))
    )
    (comp (ref "R6")
      (value "2k")
      (footprint "RESA60-630X240")
      (description "Axial Resistor, 475 Ohm, +/- 1%, 0.25 W, -55 to 155 degC, 2-Pin THD, RoHS, Bulk")
      (fields (field (name "MANUFACTURER") "Yageo") (field (name "TOLERANCE") "1%"))
      (libsource (lib "Turja Barua") (part "RES-2"))
    )
    (comp (ref "R7")
      (value "1k")
      (footprint "RESA60-630X240")
      (description "Axial Resistor, 475 Ohm, +/- 1%, 0.25 W, -55 to 155 degC, 2-Pin THD, RoHS, Bulk")
      (fields (field (name "MANUFACTURER") "Yageo") (field (name "TOLERANCE") "1%"))
      (libsource (lib "Turja Barua") (part "RES-2"))
    )
    (comp (ref "R8")
      (value "510R")
      (footprint "RESA60-630X240")
      (description "Axial Resistor, 475 Ohm, +/- 1%, 0.25 W, -55 to 155 degC, 2-Pin THD, RoHS, Bulk")
      (fields (field (name "MANUFACTURER") "Yageo") (field (name "TOLERANCE") "1%"))
      (libsource (lib "Turja Barua") (part "RES-2"))
    )
    (comp (ref "R9")
      (value "4k")
      (footprint "RESA60-630X240")
      (description "Axial Resistor, 475 Ohm, +/- 1%, 0.25 W, -55 to 155 degC, 2-Pin THD, RoHS, Bulk")
      (fields (field (name "MANUFACTURER") "Yageo") (field (name "TOLERANCE") "1%"))
      (libsource (lib "Turja Barua") (part "RES-2"))
    )
    (comp (ref "R10")
      (value "2k")
      (footprint "RESA60-630X240")
      (description "Axial Resistor, 475 Ohm, +/- 1%, 0.25 W, -55 to 155 degC, 2-Pin THD, RoHS, Bulk")
      (fields (field (name "MANUFACTURER") "Yageo") (field (name "TOLERANCE") "1%"))
      (libsource (lib "Turja Barua") (part "RES-2"))
    )
    (comp (ref "R11")
      (value "1k")
      (footprint "RESA60-630X240")
      (description "Axial Resistor, 475 Ohm, +/- 1%, 0.25 W, -55 to 155 degC, 2-Pin THD, RoHS, Bulk")
      (fields (field (name "MANUFACTURER") "Yageo") (field (name "TOLERANCE") "1%"))
      (libsource (lib "Turja Barua") (part "RES-2"))
    )
    (comp (ref "R12")
      (value "510R")
      (footprint "RESA60-630X240")
      (description "Axial Resistor, 475 Ohm, +/- 1%, 0.25 W, -55 to 155 degC, 2-Pin THD, RoHS, Bulk")
      (fields (field (name "MANUFACTURER") "Yageo") (field (name "TOLERANCE") "1%"))
      (libsource (lib "Turja Barua") (part "RES-2"))
    )
    (comp (ref "R13")
      (value "100R")
      (footprint "RESA60-630X240")
      (description "Axial Resistor, 475 Ohm, +/- 1%, 0.25 W, -55 to 155 degC, 2-Pin THD, RoHS, Bulk")
      (fields (field (name "MANUFACTURER") "Yageo") (field (name "TOLERANCE") "1%"))
      (libsource (lib "Turja Barua") (part "RES-2"))
    )
    (comp (ref "R14")
      (value "100R")
      (footprint "RESA60-630X240")
      (description "Axial Resistor, 475 Ohm, +/- 1%, 0.25 W, -55 to 155 degC, 2-Pin THD, RoHS, Bulk")
      (fields (field (name "MANUFACTURER") "Yageo") (field (name "TOLERANCE") "1%"))
      (libsource (lib "Turja Barua") (part "RES-2"))
    )
    (comp (ref "R16")
      (value "4.7k")
      (footprint "RESC0402(1005)_L")
      (description "84K5 0.063W 1% 0402 (1005 Metric)  SMD")
      (fields (field (name "POWER") "63mW") (field (name "TOLERANCE") "1%"))
      (libsource (lib "Turja Barua") (part "84D5KR2F"))
    )
    (comp (ref "R17")
      (value "4.7k")
      (footprint "RESC0402(1005)_L")
      (description "84K5 0.063W 1% 0402 (1005 Metric)  SMD")
      (fields (field (name "POWER") "63mW") (field (name "TOLERANCE") "1%"))
      (libsource (lib "Turja Barua") (part "84D5KR2F"))
    )
    (comp (ref "R18")
      (value "4.7k")
      (footprint "RESC0402(1005)_L")
      (description "84K5 0.063W 1% 0402 (1005 Metric)  SMD")
      (fields (field (name "POWER") "63mW") (field (name "TOLERANCE") "1%"))
      (libsource (lib "Turja Barua") (part "84D5KR2F"))
    )
    (comp (ref "R19")
      (value "4.7k")
      (footprint "RESC0402(1005)_L")
      (description "84K5 0.063W 1% 0402 (1005 Metric)  SMD")
      (fields (field (name "POWER") "63mW") (field (name "TOLERANCE") "1%"))
      (libsource (lib "Turja Barua") (part "84D5KR2F"))
    )
    (comp (ref "R20")
      (value "4.7k")
      (footprint "RESC0402(1005)_L")
      (description "84K5 0.063W 1% 0402 (1005 Metric)  SMD")
      (fields (field (name "POWER") "63mW") (field (name "TOLERANCE") "1%"))
      (libsource (lib "Turja Barua") (part "84D5KR2F"))
    )
    (comp (ref "R21")
      (value "4.7k")
      (footprint "RESC0402(1005)_L")
      (description "84K5 0.063W 1% 0402 (1005 Metric)  SMD")
      (fields (field (name "POWER") "63mW") (field (name "TOLERANCE") "1%"))
      (libsource (lib "Turja Barua") (part "84D5KR2F"))
    )
    (comp (ref "R22")
      (value "4.7k")
      (footprint "RESC0402(1005)_L")
      (description "84K5 0.063W 1% 0402 (1005 Metric)  SMD")
      (fields (field (name "POWER") "63mW") (field (name "TOLERANCE") "1%"))
      (libsource (lib "Turja Barua") (part "84D5KR2F"))
    )
    (comp (ref "R23")
      (value "4.7k")
      (footprint "RESC0402(1005)_L")
      (description "84K5 0.063W 1% 0402 (1005 Metric)  SMD")
      (fields (field (name "POWER") "63mW") (field (name "TOLERANCE") "1%"))
      (libsource (lib "Turja Barua") (part "84D5KR2F"))
    )
    (comp (ref "R24")
      (value "4.7k")
      (footprint "RESC0402(1005)_L")
      (description "84K5 0.063W 1% 0402 (1005 Metric)  SMD")
      (fields (field (name "POWER") "63mW") (field (name "TOLERANCE") "1%"))
      (libsource (lib "Turja Barua") (part "84D5KR2F"))
    )
    (comp (ref "R25")
      (value "24.9k")
      (footprint "RESC0402(1005)_L")
      (description "84K5 0.063W 1% 0402 (1005 Metric)  SMD")
      (fields (field (name "POWER") "63mW") (field (name "TOLERANCE") "1%"))
      (libsource (lib "Turja Barua") (part "84D5KR2F"))
    )
    (comp (ref "R26")
      (value "100k")
      (footprint "RESC0402(1005)_L")
      (description "84K5 0.063W 1% 0402 (1005 Metric)  SMD")
      (fields (field (name "POWER") "63mW") (field (name "TOLERANCE") "1%"))
      (libsource (lib "Turja Barua") (part "84D5KR2F"))
    )
    (comp (ref "R27")
      (value "100k")
      (footprint "RESC0402(1005)_L")
      (description "84K5 0.063W 1% 0402 (1005 Metric)  SMD")
      (fields (field (name "POWER") "63mW") (field (name "TOLERANCE") "1%"))
      (libsource (lib "Turja Barua") (part "84D5KR2F"))
    )
    (comp (ref "R28")
      (value "125k")
      (footprint "RESC0402(1005)_L")
      (description "84K5 0.063W 1% 0402 (1005 Metric)  SMD")
      (fields (field (name "POWER") "63mW") (field (name "TOLERANCE") "1%"))
      (libsource (lib "Turja Barua") (part "84D5KR2F"))
    )
    (comp (ref "R29")
      (value "100k")
      (footprint "RESC0402(1005)_L")
      (description "84K5 0.063W 1% 0402 (1005 Metric)  SMD")
      (fields (field (name "POWER") "63mW") (field (name "TOLERANCE") "1%"))
      (libsource (lib "Turja Barua") (part "84D5KR2F"))
    )
    (comp (ref "R30")
      (value "100k")
      (footprint "RESC0402(1005)_L")
      (description "84K5 0.063W 1% 0402 (1005 Metric)  SMD")
      (fields (field (name "POWER") "63mW") (field (name "TOLERANCE") "1%"))
      (libsource (lib "Turja Barua") (part "84D5KR2F"))
    )
    (comp (ref "R31")
      (value "100k")
      (footprint "RESC0402(1005)_L")
      (description "84K5 0.063W 1% 0402 (1005 Metric)  SMD")
      (fields (field (name "POWER") "63mW") (field (name "TOLERANCE") "1%"))
      (libsource (lib "Turja Barua") (part "84D5KR2F"))
    )
    (comp (ref "R32")
      (value "312k")
      (footprint "RESC0402(1005)_L")
      (description "84K5 0.063W 1% 0402 (1005 Metric)  SMD")
      (fields (field (name "POWER") "63mW") (field (name "TOLERANCE") "1%"))
      (libsource (lib "Turja Barua") (part "84D5KR2F"))
    )
    (comp (ref "R33")
      (value "100k")
      (footprint "RESC0402(1005)_L")
      (description "84K5 0.063W 1% 0402 (1005 Metric)  SMD")
      (fields (field (name "POWER") "63mW") (field (name "TOLERANCE") "1%"))
      (libsource (lib "Turja Barua") (part "84D5KR2F"))
    )
    (comp (ref "SW1")
      (value "25536NA6")
      (footprint "FP-25536NA6-0")
      (description "SWITCH SLIDE SPDT 4A 125V")
      (libsource (lib "Altium Content Vault") (part "52c419afdc2a387c7d548259a9aeefb"))
    )
    (comp (ref "U1")
      (value "XC7A100T-1CSG324C")
      (footprint "CSG324_XIL")
      (description "IC FPGA ARTIX7 210 I/O 324CSBGA")
      (fields (field (name "MOUSER PART NUMBER") "217-C7A100T-1CSG324C"))
      (libsource (lib "XC7A100T-1CSG324C") (part "XC7A100T-1CSG324C"))
    )
    (comp (ref "U2")
      (value "MT25QL128ABA1ESE-0SIT")
      (footprint "MICT-SE-8_L")
      (fields (field (name "MANUFACTURER") "Micron"))
      (libsource (lib "Altium Content Vault") (part "MICT-MT25QL128ABA-SOP2-8"))
    )
    (comp (ref "U3")
      (value "TPS62130ARGTR")
      (footprint "FP-RGT0016C-IPC_C")
      (description "3-V to 17-V, 3-A step-down converter with DCS-control in 3x3 QFN package 16-VQFN -40 to 125")
      (libsource (lib "Turja Barua") (part "dca50ec3578d8d47edbd046ea96d7ac"))
    )
    (comp (ref "U4")
      (value "TPS62130ARGTR")
      (footprint "FP-RGT0016C-IPC_C")
      (description "3-V to 17-V, 3-A step-down converter with DCS-control in 3x3 QFN package 16-VQFN -40 to 125")
      (libsource (lib "Turja Barua") (part "dca50ec3578d8d47edbd046ea96d7ac"))
    )
    (comp (ref "U5")
      (value "TPS62130ARGTR")
      (footprint "FP-RGT0016C-IPC_C")
      (description "3-V to 17-V, 3-A step-down converter with DCS-control in 3x3 QFN package 16-VQFN -40 to 125")
      (libsource (lib "Turja Barua") (part "dca50ec3578d8d47edbd046ea96d7ac"))
    )
    (comp (ref "X1")
      (value "DSC1001DL5-100.0000T")
      (footprint "FP-CDFN2520-4LD-PL-1-MFG")
      (libsource (lib "Altium Content Vault") (part "679220c3c234322ca52724a1007024e"))
    )
  )
  (nets
    (net (code "1") (name "/CLK100MHZ") (class "Default")
      (node (ref "U1") (pin "P17") (pinfunction "IO_L12P_T1_MRCC_14_P17") (pintype "passive"))
      (node (ref "X1") (pin "3") (pinfunction "Output_3") (pintype "passive"))
    )
    (net (code "2") (name "/HSYNC") (class "Default")
      (node (ref "R13") (pin "1") (pinfunction "1_1") (pintype "passive"))
      (node (ref "U1") (pin "H16") (pinfunction "IO_L13P_T2_MRCC_15_H16") (pintype "passive"))
    )
    (net (code "3") (name "/QSPI_CCLK") (class "Default")
      (node (ref "U1") (pin "E9") (pinfunction "CCLK_0_E9") (pintype "passive"))
      (node (ref "U2") (pin "6") (pinfunction "C_6") (pintype "input"))
    )
    (net (code "4") (name "/QSPI_CS_B") (class "Default")
      (node (ref "R16") (pin "1") (pinfunction "1_1") (pintype "passive"))
      (node (ref "U1") (pin "L13") (pinfunction "IO_L6P_T0_FCS_B_14_L13") (pintype "passive"))
      (node (ref "U2") (pin "1") (pinfunction "S#_1") (pintype "input"))
    )
    (net (code "5") (name "/QSPI_DQ0") (class "Default")
      (node (ref "U1") (pin "K17") (pinfunction "IO_L1P_T0_D00_MOSI_14_K17") (pintype "passive"))
      (node (ref "U2") (pin "5") (pinfunction "DQ0_5") (pintype "bidirectional"))
    )
    (net (code "6") (name "/QSPI_DQ1") (class "Default")
      (node (ref "U1") (pin "K18") (pinfunction "IO_L1N_T0_D01_DIN_14_K18") (pintype "passive"))
      (node (ref "U2") (pin "2") (pinfunction "DQ1_2") (pintype "bidirectional"))
    )
    (net (code "7") (name "/QSPI_DQ2") (class "Default")
      (node (ref "R17") (pin "2") (pinfunction "2_2") (pintype "passive"))
      (node (ref "U1") (pin "L14") (pinfunction "IO_L2P_T0_D02_14_L14") (pintype "passive"))
      (node (ref "U2") (pin "3") (pinfunction "W#/DQ2_3") (pintype "bidirectional"))
    )
    (net (code "8") (name "/QSPI_DQ3") (class "Default")
      (node (ref "R18") (pin "2") (pinfunction "2_2") (pintype "passive"))
      (node (ref "U1") (pin "M14") (pinfunction "IO_L2N_T0_D03_14_M14") (pintype "passive"))
      (node (ref "U2") (pin "7") (pinfunction "HOLD#/DQ3_7") (pintype "bidirectional"))
    )
    (net (code "9") (name "/SW0") (class "Default")
      (node (ref "SW1") (pin "2") (pinfunction "2_2") (pintype "passive"))
      (node (ref "U1") (pin "F15") (pinfunction "IO_L14P_T2_SRCC_15_F15") (pintype "passive"))
    )
    (net (code "10") (name "/TCK") (class "Default")
      (node (ref "C1") (pin "1") (pinfunction "1_1") (pintype "passive"))
      (node (ref "C18") (pin "2") (pinfunction "2_2") (pintype "passive"))
      (node (ref "C19") (pin "2") (pinfunction "2_2") (pintype "passive"))
      (node (ref "C20") (pin "2") (pinfunction "2_2") (pintype "passive"))
      (node (ref "C21") (pin "2") (pinfunction "2_2") (pintype "passive"))
      (node (ref "C22") (pin "2") (pinfunction "2_2") (pintype "passive"))
      (node (ref "C23") (pin "2") (pinfunction "2_2") (pintype "passive"))
      (node (ref "C24") (pin "2") (pinfunction "2_2") (pintype "passive"))
      (node (ref "C25") (pin "2") (pinfunction "2_2") (pintype "passive"))
      (node (ref "C26") (pin "2") (pinfunction "2_2") (pintype "passive"))
      (node (ref "C27") (pin "2") (pinfunction "2_2") (pintype "passive"))
      (node (ref "C28") (pin "2") (pinfunction "2_2") (pintype "passive"))
      (node (ref "C29") (pin "1") (pinfunction "1_1") (pintype "passive"))
      (node (ref "C30") (pin "2") (pinfunction "2_2") (pintype "passive"))
      (node (ref "C31") (pin "1") (pinfunction "1_1") (pintype "passive"))
      (node (ref "C32") (pin "1") (pinfunction "1_1") (pintype "passive"))
      (node (ref "C33") (pin "1") (pinfunction "1_1") (pintype "passive"))
      (node (ref "C34") (pin "1") (pinfunction "1_1") (pintype "passive"))
      (node (ref "C35") (pin "1") (pinfunction "1_1") (pintype "passive"))
      (node (ref "C36") (pin "1") (pinfunction "1_1") (pintype "passive"))
      (node (ref "C37") (pin "1") (pinfunction "1_1") (pintype "passive"))
      (node (ref "C38") (pin "1") (pinfunction "1_1") (pintype "passive"))
      (node (ref "C39") (pin "1") (pinfunction "1_1") (pintype "passive"))
      (node (ref "C40") (pin "1") (pinfunction "1_1") (pintype "passive"))
      (node (ref "C41") (pin "1") (pinfunction "1_1") (pintype "passive"))
      (node (ref "C42") (pin "1") (pinfunction "1_1") (pintype "passive"))
      (node (ref "C53") (pin "2") (pinfunction "2_2") (pintype "passive"))
      (node (ref "C57") (pin "2") (pinfunction "2_2") (pintype "passive"))
      (node (ref "C59") (pin "1") (pinfunction "1_1") (pintype "passive"))
      (node (ref "C61") (pin "1") (pinfunction "1_1") (pintype "passive"))
      (node (ref "J2") (pin "1") (pinfunction "1_1") (pintype "passive"))
      (node (ref "L3") (pin "2") (pinfunction "2_2") (pintype "passive"))
      (node (ref "R16") (pin "2") (pinfunction "2_2") (pintype "passive"))
      (node (ref "R17") (pin "1") (pinfunction "1_1") (pintype "passive"))
      (node (ref "R18") (pin "1") (pinfunction "1_1") (pintype "passive"))
      (node (ref "R19") (pin "2") (pinfunction "2_2") (pintype "passive"))
      (node (ref "R22") (pin "2") (pinfunction "2_2") (pintype "passive"))
      (node (ref "R23") (pin "2") (pinfunction "2_2") (pintype "passive"))
      (node (ref "R24") (pin "2") (pinfunction "2_2") (pintype "passive"))
      (node (ref "R32") (pin "1") (pinfunction "1_1") (pintype "passive"))
      (node (ref "R33") (pin "2") (pinfunction "2_2") (pintype "passive"))
      (node (ref "SW1") (pin "1") (pinfunction "1_1") (pintype "passive"))
      (node (ref "U1") (pin "A17") (pinfunction "VCCO_15_1_A17") (pintype "passive"))
      (node (ref "U1") (pin "A7") (pinfunction "VCCO_35_1_A7") (pintype "passive"))
      (node (ref "U1") (pin "B10") (pinfunction "VCCO_16_B10") (pintype "passive"))
      (node (ref "U1") (pin "C13") (pinfunction "VCCO_15_2_C13") (pintype "passive"))
      (node (ref "U1") (pin "C3") (pinfunction "VCCO_35_2_C3") (pintype "passive"))
      (node (ref "U1") (pin "D16") (pinfunction "VCCO_15_3_D16") (pintype "passive"))
      (node (ref "U1") (pin "D6") (pinfunction "VCCO_35_3_D6") (pintype "passive"))
      (node (ref "U1") (pin "E10") (pinfunction "TCK_0_E10") (pintype "passive"))
      (node (ref "U1") (pin "F2") (pinfunction "VCCO_35_4_F2") (pintype "passive"))
      (node (ref "U1") (pin "G15") (pinfunction "VCCO_15_4_G15") (pintype "passive"))
      (node (ref "U1") (pin "G5") (pinfunction "VCCO_35_5_G5") (pintype "passive"))
      (node (ref "U1") (pin "H18") (pinfunction "VCCO_15_5_H18") (pintype "passive"))
      (node (ref "U1") (pin "J1") (pinfunction "VCCO_35_6_J1") (pintype "passive"))
      (node (ref "U1") (pin "K14") (pinfunction "VCCO_15_6_K14") (pintype "passive"))
      (node (ref "U1") (pin "K4") (pinfunction "VCCO_34_1_K4") (pintype "passive"))
      (node (ref "U1") (pin "L17") (pinfunction "VCCO_14_1_L17") (pintype "passive"))
      (node (ref "U1") (pin "N13") (pinfunction "VCCO_14_2_N13") (pintype "passive"))
      (node (ref "U1") (pin "N3") (pinfunction "VCCO_34_2_N3") (pintype "passive"))
      (node (ref "U1") (pin "P16") (pinfunction "VCCO_14_3_P16") (pintype "passive"))
      (node (ref "U1") (pin "P6") (pinfunction "VCCO_34_3_P6") (pintype "passive"))
      (node (ref "U1") (pin "P8") (pinfunction "CFGBVS_0_P8") (pintype "passive"))
      (node (ref "U1") (pin "R9") (pinfunction "VCCO_0_R9") (pintype "passive"))
      (node (ref "U1") (pin "T12") (pinfunction "VCCO_14_4_T12") (pintype "passive"))
      (node (ref "U1") (pin "T2") (pinfunction "VCCO_34_4_T2") (pintype "passive"))
      (node (ref "U1") (pin "U15") (pinfunction "VCCO_14_5_U15") (pintype "passive"))
      (node (ref "U1") (pin "U5") (pinfunction "VCCO_34_5_U5") (pintype "passive"))
      (node (ref "U1") (pin "V18") (pinfunction "VCCO_14_6_V18") (pintype "passive"))
      (node (ref "U1") (pin "V8") (pinfunction "VCCO_34_6_V8") (pintype "passive"))
      (node (ref "U2") (pin "8") (pinfunction "VCC_8") (pintype "power_in"))
      (node (ref "U5") (pin "14") (pinfunction "VOS_14") (pintype "input"))
      (node (ref "X1") (pin "1") (pinfunction "~{Standby}_1") (pintype "input"))
      (node (ref "X1") (pin "4") (pinfunction "VDD_4") (pintype "power_in"))
    )
    (net (code "11") (name "/TDI") (class "Default")
      (node (ref "J2") (pin "5") (pinfunction "5_5") (pintype "passive"))
      (node (ref "U1") (pin "E11") (pinfunction "TDI_0_E11") (pintype "passive"))
    )
    (net (code "12") (name "/TDO") (class "Default")
      (node (ref "J2") (pin "3") (pinfunction "3_3") (pintype "passive"))
      (node (ref "U1") (pin "E13") (pinfunction "TDO_0_E13") (pintype "passive"))
    )
    (net (code "13") (name "/TMS") (class "Default")
      (node (ref "J2") (pin "7") (pinfunction "7_7") (pintype "passive"))
      (node (ref "U1") (pin "E12") (pinfunction "TMS_0_E12") (pintype "passive"))
    )
    (net (code "14") (name "/VCCAUX_1V8") (class "Default")
      (node (ref "C15") (pin "2") (pinfunction "2_2") (pintype "passive"))
      (node (ref "C16") (pin "1") (pinfunction "1_1") (pintype "passive"))
      (node (ref "C17") (pin "1") (pinfunction "1_1") (pintype "passive"))
      (node (ref "C50") (pin "2") (pinfunction "2_2") (pintype "passive"))
      (node (ref "C51") (pin "2") (pinfunction "2_2") (pintype "passive"))
      (node (ref "C66") (pin "2") (pinfunction "2_2") (pintype "passive"))
      (node (ref "L2") (pin "2") (pinfunction "2_2") (pintype "passive"))
      (node (ref "R28") (pin "1") (pinfunction "1_1") (pintype "passive"))
      (node (ref "R30") (pin "2") (pinfunction "2_2") (pintype "passive"))
      (node (ref "U1") (pin "F12") (pinfunction "VCCAUX_1_F12") (pintype "passive"))
      (node (ref "U1") (pin "H10") (pinfunction "VCCADC_0_H10") (pintype "passive"))
      (node (ref "U1") (pin "H12") (pinfunction "VCCAUX_2_H12") (pintype "passive"))
      (node (ref "U1") (pin "K12") (pinfunction "VCCAUX_3_K12") (pintype "passive"))
      (node (ref "U1") (pin "M12") (pinfunction "VCCAUX_4_M12") (pintype "passive"))
      (node (ref "U4") (pin "14") (pinfunction "VOS_14") (pintype "input"))
    )
    (net (code "15") (name "/VCCAUX_FB") (class "Default")
      (node (ref "R28") (pin "2") (pinfunction "2_2") (pintype "passive"))
      (node (ref "R29") (pin "1") (pinfunction "1_1") (pintype "passive"))
      (node (ref "U4") (pin "5") (pinfunction "FB_5") (pintype "input"))
    )
    (net (code "16") (name "/VCCAUX_PG") (class "Default")
      (node (ref "R30") (pin "1") (pinfunction "1_1") (pintype "passive"))
      (node (ref "U4") (pin "4") (pinfunction "PG_4") (pintype "output"))
    )
    (net (code "17") (name "/VCCAUX_SS") (class "Default")
      (node (ref "C52") (pin "2") (pinfunction "2_2") (pintype "passive"))
      (node (ref "U4") (pin "9") (pinfunction "SS/TR_9") (pintype "input"))
    )
    (net (code "18") (name "/VCCAUX_SW") (class "Default")
      (node (ref "L2") (pin "1") (pinfunction "1_1") (pintype "passive"))
      (node (ref "U4") (pin "1") (pinfunction "SW_1") (pintype "output"))
      (node (ref "U4") (pin "2") (pinfunction "SW_2") (pintype "output"))
      (node (ref "U4") (pin "3") (pinfunction "SW_3") (pintype "output"))
    )
    (net (code "19") (name "/VCCINT_1V0") (class "Default")
      (node (ref "C10") (pin "2") (pinfunction "2_2") (pintype "passive"))
      (node (ref "C11") (pin "2") (pinfunction "2_2") (pintype "passive"))
      (node (ref "C12") (pin "2") (pinfunction "2_2") (pintype "passive"))
      (node (ref "C13") (pin "2") (pinfunction "2_2") (pintype "passive"))
      (node (ref "C14") (pin "2") (pinfunction "2_2") (pintype "passive"))
      (node (ref "C2") (pin "1") (pinfunction "1_1") (pintype "passive"))
      (node (ref "C3") (pin "1") (pinfunction "1_1") (pintype "passive"))
      (node (ref "C4") (pin "1") (pinfunction "1_1") (pintype "passive"))
      (node (ref "C45") (pin "2") (pinfunction "2_2") (pintype "passive"))
      (node (ref "C46") (pin "2") (pinfunction "2_2") (pintype "passive"))
      (node (ref "C5") (pin "1") (pinfunction "1_1") (pintype "passive"))
      (node (ref "C6") (pin "2") (pinfunction "2_2") (pintype "passive"))
      (node (ref "C60") (pin "2") (pinfunction "2_2") (pintype "passive"))
      (node (ref "C63") (pin "2") (pinfunction "2_2") (pintype "passive"))
      (node (ref "C7") (pin "1") (pinfunction "1_1") (pintype "passive"))
      (node (ref "C8") (pin "1") (pinfunction "1_1") (pintype "passive"))
      (node (ref "C9") (pin "1") (pinfunction "1_1") (pintype "passive"))
      (node (ref "L1") (pin "2") (pinfunction "2_2") (pintype "passive"))
      (node (ref "R25") (pin "1") (pinfunction "1_1") (pintype "passive"))
      (node (ref "R27") (pin "2") (pinfunction "2_2") (pintype "passive"))
      (node (ref "U1") (pin "F10") (pinfunction "VCCBRAM_1_F10") (pintype "passive"))
      (node (ref "U1") (pin "F8") (pinfunction "VCCINT_1_F8") (pintype "passive"))
      (node (ref "U1") (pin "G11") (pinfunction "VCCBRAM_2_G11") (pintype "passive"))
      (node (ref "U1") (pin "G7") (pinfunction "VCCINT_2_G7") (pintype "passive"))
      (node (ref "U1") (pin "G9") (pinfunction "VCCINT_3_G9") (pintype "passive"))
      (node (ref "U1") (pin "H8") (pinfunction "VCCINT_4_H8") (pintype "passive"))
      (node (ref "U1") (pin "J11") (pinfunction "VCCINT_6_J11") (pintype "passive"))
      (node (ref "U1") (pin "J7") (pinfunction "VCCINT_5_J7") (pintype "passive"))
      (node (ref "U1") (pin "K8") (pinfunction "VCCINT_7_K8") (pintype "passive"))
      (node (ref "U1") (pin "L11") (pinfunction "VCCINT_9_L11") (pintype "passive"))
      (node (ref "U1") (pin "L7") (pinfunction "VCCINT_8_L7") (pintype "passive"))
      (node (ref "U1") (pin "M10") (pinfunction "VCCINT_11_M10") (pintype "passive"))
      (node (ref "U1") (pin "M8") (pinfunction "VCCINT_10_M8") (pintype "passive"))
      (node (ref "U1") (pin "N11") (pinfunction "VCCINT_14_N11") (pintype "passive"))
      (node (ref "U1") (pin "N7") (pinfunction "VCCINT_12_N7") (pintype "passive"))
      (node (ref "U1") (pin "N9") (pinfunction "VCCINT_13_N9") (pintype "passive"))
      (node (ref "U3") (pin "14") (pinfunction "VOS_14") (pintype "input"))
    )
    (net (code "20") (name "/VCCINT_FB") (class "Default")
      (node (ref "R25") (pin "2") (pinfunction "2_2") (pintype "passive"))
      (node (ref "R26") (pin "1") (pinfunction "1_1") (pintype "passive"))
      (node (ref "U3") (pin "5") (pinfunction "FB_5") (pintype "input"))
    )
    (net (code "21") (name "/VCCINT_PG") (class "Default")
      (node (ref "R27") (pin "1") (pinfunction "1_1") (pintype "passive"))
      (node (ref "U3") (pin "4") (pinfunction "PG_4") (pintype "output"))
    )
    (net (code "22") (name "/VCCINT_SS") (class "Default")
      (node (ref "C47") (pin "2") (pinfunction "2_2") (pintype "passive"))
      (node (ref "U3") (pin "9") (pinfunction "SS/TR_9") (pintype "input"))
    )
    (net (code "23") (name "/VCCINT_SW") (class "Default")
      (node (ref "L1") (pin "1") (pinfunction "1_1") (pintype "passive"))
      (node (ref "U3") (pin "1") (pinfunction "SW_1") (pintype "output"))
      (node (ref "U3") (pin "2") (pinfunction "SW_2") (pintype "output"))
      (node (ref "U3") (pin "3") (pinfunction "SW_3") (pintype "output"))
    )
    (net (code "24") (name "/VCCO_FB") (class "Default")
      (node (ref "R31") (pin "1") (pinfunction "1_1") (pintype "passive"))
      (node (ref "R32") (pin "2") (pinfunction "2_2") (pintype "passive"))
      (node (ref "U5") (pin "5") (pinfunction "FB_5") (pintype "input"))
    )
    (net (code "25") (name "/VCCO_PG") (class "Default")
      (node (ref "R33") (pin "1") (pinfunction "1_1") (pintype "passive"))
      (node (ref "U5") (pin "4") (pinfunction "PG_4") (pintype "output"))
    )
    (net (code "26") (name "/VCCO_SS") (class "Default")
      (node (ref "C56") (pin "2") (pinfunction "2_2") (pintype "passive"))
      (node (ref "U5") (pin "9") (pinfunction "SS/TR_9") (pintype "input"))
    )
    (net (code "27") (name "/VCCO_SW") (class "Default")
      (node (ref "L3") (pin "1") (pinfunction "1_1") (pintype "passive"))
      (node (ref "U5") (pin "1") (pinfunction "SW_1") (pintype "output"))
      (node (ref "U5") (pin "2") (pinfunction "SW_2") (pintype "output"))
      (node (ref "U5") (pin "3") (pinfunction "SW_3") (pintype "output"))
    )
    (net (code "28") (name "/VGA_B0") (class "Default")
      (node (ref "R9") (pin "1") (pinfunction "1_1") (pintype "passive"))
      (node (ref "U1") (pin "E15") (pinfunction "IO_L11P_T1_SRCC_15_E15") (pintype "passive"))
    )
    (net (code "29") (name "/VGA_B1") (class "Default")
      (node (ref "R10") (pin "1") (pinfunction "1_1") (pintype "passive"))
      (node (ref "U1") (pin "C15") (pinfunction "IO_L12N_T1_MRCC_15_C15") (pintype "passive"))
    )
    (net (code "30") (name "/VGA_B2") (class "Default")
      (node (ref "R11") (pin "1") (pinfunction "1_1") (pintype "passive"))
      (node (ref "U1") (pin "D15") (pinfunction "IO_L12P_T1_MRCC_15_D15") (pintype "passive"))
    )
    (net (code "31") (name "/VGA_B3") (class "Default")
      (node (ref "R12") (pin "1") (pinfunction "1_1") (pintype "passive"))
      (node (ref "U1") (pin "G16") (pinfunction "IO_L13N_T2_MRCC_15_G16") (pintype "passive"))
    )
    (net (code "32") (name "/VGA_B_ANALOG") (class "Default")
      (node (ref "J1") (pin "3") (pinfunction "3_3") (pintype "passive"))
      (node (ref "R10") (pin "2") (pinfunction "2_2") (pintype "passive"))
      (node (ref "R11") (pin "2") (pinfunction "2_2") (pintype "passive"))
      (node (ref "R12") (pin "2") (pinfunction "2_2") (pintype "passive"))
      (node (ref "R9") (pin "2") (pinfunction "2_2") (pintype "passive"))
    )
    (net (code "33") (name "/VGA_G0") (class "Default")
      (node (ref "R5") (pin "1") (pinfunction "1_1") (pintype "passive"))
      (node (ref "U1") (pin "E18") (pinfunction "IO_L21P_T3_DQS_15_E18") (pintype "passive"))
    )
    (net (code "34") (name "/VGA_G1") (class "Default")
      (node (ref "R6") (pin "1") (pinfunction "1_1") (pintype "passive"))
      (node (ref "U1") (pin "G13") (pinfunction "IO_0_15_G13") (pintype "passive"))
    )
    (net (code "35") (name "/VGA_G2") (class "Default")
      (node (ref "R7") (pin "1") (pinfunction "1_1") (pintype "passive"))
      (node (ref "U1") (pin "K16") (pinfunction "IO_25_15_K16") (pintype "passive"))
    )
    (net (code "36") (name "/VGA_G3") (class "Default")
      (node (ref "R8") (pin "1") (pinfunction "1_1") (pintype "passive"))
      (node (ref "U1") (pin "E16") (pinfunction "IO_L11N_T1_SRCC_15_E16") (pintype "passive"))
    )
    (net (code "37") (name "/VGA_G_ANALOG") (class "Default")
      (node (ref "J1") (pin "2") (pinfunction "2_2") (pintype "passive"))
      (node (ref "R5") (pin "2") (pinfunction "2_2") (pintype "passive"))
      (node (ref "R6") (pin "2") (pinfunction "2_2") (pintype "passive"))
      (node (ref "R7") (pin "2") (pinfunction "2_2") (pintype "passive"))
      (node (ref "R8") (pin "2") (pinfunction "2_2") (pintype "passive"))
    )
    (net (code "38") (name "/VGA_HSYNC") (class "Default")
      (node (ref "J1") (pin "13") (pinfunction "13_13") (pintype "passive"))
      (node (ref "R13") (pin "2") (pinfunction "2_2") (pintype "passive"))
    )
    (net (code "39") (name "/VGA_R0") (class "Default")
      (node (ref "R1") (pin "1") (pinfunction "1_1") (pintype "passive"))
      (node (ref "U1") (pin "A11") (pinfunction "IO_L4N_T0_15_A11") (pintype "passive"))
    )
    (net (code "40") (name "/VGA_R1") (class "Default")
      (node (ref "R2") (pin "1") (pinfunction "1_1") (pintype "passive"))
      (node (ref "U1") (pin "B11") (pinfunction "IO_L4P_T0_15_B11") (pintype "passive"))
    )
    (net (code "41") (name "/VGA_R2") (class "Default")
      (node (ref "R3") (pin "1") (pinfunction "1_1") (pintype "passive"))
      (node (ref "U1") (pin "D12") (pinfunction "IO_L6P_T0_15_D12") (pintype "passive"))
    )
    (net (code "42") (name "/VGA_R3") (class "Default")
      (node (ref "R4") (pin "1") (pinfunction "1_1") (pintype "passive"))
      (node (ref "U1") (pin "H14") (pinfunction "IO_L15P_T2_DQS_15_H14") (pintype "passive"))
    )
    (net (code "43") (name "/VGA_R_ANALOG") (class "Default")
      (node (ref "J1") (pin "1") (pinfunction "1_1") (pintype "passive"))
      (node (ref "R1") (pin "2") (pinfunction "2_2") (pintype "passive"))
      (node (ref "R2") (pin "2") (pinfunction "2_2") (pintype "passive"))
      (node (ref "R3") (pin "2") (pinfunction "2_2") (pintype "passive"))
      (node (ref "R4") (pin "2") (pinfunction "2_2") (pintype "passive"))
    )
    (net (code "44") (name "/VGA_VSYNC") (class "Default")
      (node (ref "J1") (pin "14") (pinfunction "14_14") (pintype "passive"))
      (node (ref "R14") (pin "2") (pinfunction "2_2") (pintype "passive"))
    )
    (net (code "45") (name "/VIN") (class "Default")
      (node (ref "C44") (pin "2") (pinfunction "2_2") (pintype "passive"))
      (node (ref "C48") (pin "2") (pinfunction "2_2") (pintype "passive"))
      (node (ref "C49") (pin "2") (pinfunction "2_2") (pintype "passive"))
      (node (ref "C54") (pin "2") (pinfunction "2_2") (pintype "passive"))
      (node (ref "C55") (pin "2") (pinfunction "2_2") (pintype "passive"))
      (node (ref "C62") (pin "2") (pinfunction "2_2") (pintype "passive"))
      (node (ref "C64") (pin "1") (pinfunction "1_1") (pintype "passive"))
      (node (ref "C65") (pin "2") (pinfunction "2_2") (pintype "passive"))
      (node (ref "J3") (pin "1") (pinfunction "1_1") (pintype "passive"))
      (node (ref "U3") (pin "10") (pinfunction "AVIN_10") (pintype "input"))
      (node (ref "U3") (pin "11") (pinfunction "PVIN_11") (pintype "input"))
      (node (ref "U3") (pin "12") (pinfunction "PVIN_12") (pintype "input"))
      (node (ref "U3") (pin "13") (pinfunction "EN_13") (pintype "input"))
      (node (ref "U4") (pin "10") (pinfunction "AVIN_10") (pintype "input"))
      (node (ref "U4") (pin "11") (pinfunction "PVIN_11") (pintype "input"))
      (node (ref "U4") (pin "12") (pinfunction "PVIN_12") (pintype "input"))
      (node (ref "U4") (pin "13") (pinfunction "EN_13") (pintype "input"))
      (node (ref "U5") (pin "10") (pinfunction "AVIN_10") (pintype "input"))
      (node (ref "U5") (pin "11") (pinfunction "PVIN_11") (pintype "input"))
      (node (ref "U5") (pin "12") (pinfunction "PVIN_12") (pintype "input"))
      (node (ref "U5") (pin "13") (pinfunction "EN_13") (pintype "input"))
    )
    (net (code "46") (name "/VSYNC") (class "Default")
      (node (ref "R14") (pin "1") (pinfunction "1_1") (pintype "passive"))
      (node (ref "U1") (pin "F16") (pinfunction "IO_L14N_T2_SRCC_15_F16") (pintype "passive"))
    )
    (net (code "47") (name "GND") (class "Default")
      (node (ref "C1") (pin "2") (pinfunction "2_2") (pintype "passive"))
      (node (ref "C10") (pin "1") (pinfunction "1_1") (pintype "passive"))
      (node (ref "C11") (pin "1") (pinfunction "1_1") (pintype "passive"))
      (node (ref "C12") (pin "1") (pinfunction "1_1") (pintype "passive"))
      (node (ref "C13") (pin "1") (pinfunction "1_1") (pintype "passive"))
      (node (ref "C14") (pin "1") (pinfunction "1_1") (pintype "passive"))
      (node (ref "C15") (pin "1") (pinfunction "1_1") (pintype "passive"))
      (node (ref "C16") (pin "2") (pinfunction "2_2") (pintype "passive"))
      (node (ref "C17") (pin "2") (pinfunction "2_2") (pintype "passive"))
      (node (ref "C18") (pin "1") (pinfunction "1_1") (pintype "passive"))
      (node (ref "C19") (pin "1") (pinfunction "1_1") (pintype "passive"))
      (node (ref "C2") (pin "2") (pinfunction "2_2") (pintype "passive"))
      (node (ref "C20") (pin "1") (pinfunction "1_1") (pintype "passive"))
      (node (ref "C21") (pin "1") (pinfunction "1_1") (pintype "passive"))
      (node (ref "C22") (pin "1") (pinfunction "1_1") (pintype "passive"))
      (node (ref "C23") (pin "1") (pinfunction "1_1") (pintype "passive"))
      (node (ref "C24") (pin "1") (pinfunction "1_1") (pintype "passive"))
      (node (ref "C25") (pin "1") (pinfunction "1_1") (pintype "passive"))
      (node (ref "C26") (pin "1") (pinfunction "1_1") (pintype "passive"))
      (node (ref "C27") (pin "1") (pinfunction "1_1") (pintype "passive"))
      (node (ref "C28") (pin "1") (pinfunction "1_1") (pintype "passive"))
      (node (ref "C29") (pin "2") (pinfunction "2_2") (pintype "passive"))
      (node (ref "C3") (pin "2") (pinfunction "2_2") (pintype "passive"))
      (node (ref "C30") (pin "1") (pinfunction "1_1") (pintype "passive"))
      (node (ref "C31") (pin "2") (pinfunction "2_2") (pintype "passive"))
      (node (ref "C32") (pin "2") (pinfunction "2_2") (pintype "passive"))
      (node (ref "C33") (pin "2") (pinfunction "2_2") (pintype "passive"))
      (node (ref "C34") (pin "2") (pinfunction "2_2") (pintype "passive"))
      (node (ref "C35") (pin "2") (pinfunction "2_2") (pintype "passive"))
      (node (ref "C36") (pin "2") (pinfunction "2_2") (pintype "passive"))
      (node (ref "C37") (pin "2") (pinfunction "2_2") (pintype "passive"))
      (node (ref "C38") (pin "2") (pinfunction "2_2") (pintype "passive"))
      (node (ref "C39") (pin "2") (pinfunction "2_2") (pintype "passive"))
      (node (ref "C4") (pin "2") (pinfunction "2_2") (pintype "passive"))
      (node (ref "C40") (pin "2") (pinfunction "2_2") (pintype "passive"))
      (node (ref "C41") (pin "2") (pinfunction "2_2") (pintype "passive"))
      (node (ref "C42") (pin "2") (pinfunction "2_2") (pintype "passive"))
      (node (ref "C44") (pin "1") (pinfunction "1_1") (pintype "passive"))
      (node (ref "C45") (pin "1") (pinfunction "1_1") (pintype "passive"))
      (node (ref "C46") (pin "1") (pinfunction "1_1") (pintype "passive"))
      (node (ref "C47") (pin "1") (pinfunction "1_1") (pintype "passive"))
      (node (ref "C48") (pin "1") (pinfunction "1_1") (pintype "passive"))
      (node (ref "C49") (pin "1") (pinfunction "1_1") (pintype "passive"))
      (node (ref "C5") (pin "2") (pinfunction "2_2") (pintype "passive"))
      (node (ref "C50") (pin "1") (pinfunction "1_1") (pintype "passive"))
      (node (ref "C51") (pin "1") (pinfunction "1_1") (pintype "passive"))
      (node (ref "C52") (pin "1") (pinfunction "1_1") (pintype "passive"))
      (node (ref "C53") (pin "1") (pinfunction "1_1") (pintype "passive"))
      (node (ref "C54") (pin "1") (pinfunction "1_1") (pintype "passive"))
      (node (ref "C55") (pin "1") (pinfunction "1_1") (pintype "passive"))
      (node (ref "C56") (pin "1") (pinfunction "1_1") (pintype "passive"))
      (node (ref "C57") (pin "1") (pinfunction "1_1") (pintype "passive"))
      (node (ref "C59") (pin "2") (pinfunction "2_2") (pintype "passive"))
      (node (ref "C6") (pin "1") (pinfunction "1_1") (pintype "passive"))
      (node (ref "C60") (pin "1") (pinfunction "1_1") (pintype "passive"))
      (node (ref "C61") (pin "2") (pinfunction "2_2") (pintype "passive"))
      (node (ref "C62") (pin "1") (pinfunction "1_1") (pintype "passive"))
      (node (ref "C63") (pin "1") (pinfunction "1_1") (pintype "passive"))
      (node (ref "C64") (pin "2") (pinfunction "2_2") (pintype "passive"))
      (node (ref "C65") (pin "1") (pinfunction "1_1") (pintype "passive"))
      (node (ref "C66") (pin "1") (pinfunction "1_1") (pintype "passive"))
      (node (ref "C7") (pin "2") (pinfunction "2_2") (pintype "passive"))
      (node (ref "C8") (pin "2") (pinfunction "2_2") (pintype "passive"))
      (node (ref "C9") (pin "2") (pinfunction "2_2") (pintype "passive"))
      (node (ref "J1") (pin "10") (pinfunction "10_10") (pintype "passive"))
      (node (ref "J1") (pin "11") (pinfunction "11_11") (pintype "passive"))
      (node (ref "J1") (pin "12") (pinfunction "12_12") (pintype "passive"))
      (node (ref "J1") (pin "15") (pinfunction "15_15") (pintype "passive"))
      (node (ref "J1") (pin "4") (pinfunction "4_4") (pintype "passive"))
      (node (ref "J1") (pin "5") (pinfunction "5_5") (pintype "passive"))
      (node (ref "J1") (pin "6") (pinfunction "6_6") (pintype "passive"))
      (node (ref "J1") (pin "7") (pinfunction "7_7") (pintype "passive"))
      (node (ref "J1") (pin "8") (pinfunction "8_8") (pintype "passive"))
      (node (ref "J1") (pin "9") (pinfunction "9_9") (pintype "passive"))
      (node (ref "J1") (pin "M1") (pinfunction "M1_M1") (pintype "passive"))
      (node (ref "J1") (pin "M2") (pinfunction "M2_M2") (pintype "passive"))
      (node (ref "J2") (pin "10") (pinfunction "10_10") (pintype "passive"))
      (node (ref "J2") (pin "2") (pinfunction "2_2") (pintype "passive"))
      (node (ref "J2") (pin "4") (pinfunction "4_4") (pintype "passive"))
      (node (ref "J2") (pin "6") (pinfunction "6_6") (pintype "passive"))
      (node (ref "J2") (pin "8") (pinfunction "8_8") (pintype "passive"))
      (node (ref "J3") (pin "2") (pinfunction "2_2") (pintype "passive"))
      (node (ref "R20") (pin "2") (pinfunction "2_2") (pintype "passive"))
      (node (ref "R21") (pin "2") (pinfunction "2_2") (pintype "passive"))
      (node (ref "R26") (pin "2") (pinfunction "2_2") (pintype "passive"))
      (node (ref "R29") (pin "2") (pinfunction "2_2") (pintype "passive"))
      (node (ref "R31") (pin "2") (pinfunction "2_2") (pintype "passive"))
      (node (ref "SW1") (pin "3") (pinfunction "3_3") (pintype "passive"))
      (node (ref "U1") (pin "A12") (pinfunction "GND_2_A12") (pintype "passive"))
      (node (ref "U1") (pin "A2") (pinfunction "GND_1_A2") (pintype "passive"))
      (node (ref "U1") (pin "B15") (pinfunction "GND_4_B15") (pintype "passive"))
      (node (ref "U1") (pin "B5") (pinfunction "GND_3_B5") (pintype "passive"))
      (node (ref "U1") (pin "C18") (pinfunction "GND_6_C18") (pintype "passive"))
      (node (ref "U1") (pin "C8") (pinfunction "GND_5_C8") (pintype "passive"))
      (node (ref "U1") (pin "D1") (pinfunction "GND_7_D1") (pintype "passive"))
      (node (ref "U1") (pin "D11") (pinfunction "GND_8_D11") (pintype "passive"))
      (node (ref "U1") (pin "E14") (pinfunction "GND_10_E14") (pintype "passive"))
      (node (ref "U1") (pin "E4") (pinfunction "GND_9_E4") (pintype "passive"))
      (node (ref "U1") (pin "E8") (pinfunction "VCCBATT_0_E8") (pintype "passive"))
      (node (ref "U1") (pin "F11") (pinfunction "GND_13_F11") (pintype "passive"))
      (node (ref "U1") (pin "F17") (pinfunction "GND_14_F17") (pintype "passive"))
      (node (ref "U1") (pin "F7") (pinfunction "GND_11_F7") (pintype "passive"))
      (node (ref "U1") (pin "F9") (pinfunction "GND_12_F9") (pintype "passive"))
      (node (ref "U1") (pin "G10") (pinfunction "GND_16_G10") (pintype "passive"))
      (node (ref "U1") (pin "G12") (pinfunction "GND_17_G12") (pintype "passive"))
      (node (ref "U1") (pin "G8") (pinfunction "GND_15_G8") (pintype "passive"))
      (node (ref "U1") (pin "H11") (pinfunction "GND_20_H11") (pintype "passive"))
      (node (ref "U1") (pin "H13") (pinfunction "GND_21_H13") (pintype "passive"))
      (node (ref "U1") (pin "H3") (pinfunction "GND_18_H3") (pintype "passive"))
      (node (ref "U1") (pin "H7") (pinfunction "GND_19_H7") (pintype "passive"))
      (node (ref "U1") (pin "H9") (pinfunction "GNDADC_0_H9") (pintype "passive"))
      (node (ref "U1") (pin "J10") (pinfunction "VP_0_J10") (pintype "passive"))
      (node (ref "U1") (pin "J12") (pinfunction "GND_24_J12") (pintype "passive"))
      (node (ref "U1") (pin "J16") (pinfunction "GND_25_J16") (pintype "passive"))
      (node (ref "U1") (pin "J6") (pinfunction "GND_22_J6") (pintype "passive"))
      (node (ref "U1") (pin "J8") (pinfunction "GND_23_J8") (pintype "passive"))
      (node (ref "U1") (pin "K11") (pinfunction "GND_27_K11") (pintype "passive"))
      (node (ref "U1") (pin "K7") (pinfunction "GND_26_K7") (pintype "passive"))
      (node (ref "U1") (pin "K9") (pinfunction "VN_0_K9") (pintype "passive"))
      (node (ref "U1") (pin "L12") (pinfunction "GND_30_L12") (pintype "passive"))
      (node (ref "U1") (pin "L2") (pinfunction "GND_28_L2") (pintype "passive"))
      (node (ref "U1") (pin "L8") (pinfunction "GND_29_L8") (pintype "passive"))
      (node (ref "U1") (pin "M11") (pinfunction "GND_34_M11") (pintype "passive"))
      (node (ref "U1") (pin "M15") (pinfunction "GND_35_M15") (pintype "passive"))
      (node (ref "U1") (pin "M5") (pinfunction "GND_31_M5") (pintype "passive"))
      (node (ref "U1") (pin "M7") (pinfunction "GND_32_M7") (pintype "passive"))
      (node (ref "U1") (pin "M9") (pinfunction "GND_33_M9") (pintype "passive"))
      (node (ref "U1") (pin "N10") (pinfunction "GND_37_N10") (pintype "passive"))
      (node (ref "U1") (pin "N12") (pinfunction "GND_38_N12") (pintype "passive"))
      (node (ref "U1") (pin "N18") (pinfunction "GND_39_N18") (pintype "passive"))
      (node (ref "U1") (pin "N8") (pinfunction "GND_36_N8") (pintype "passive"))
      (node (ref "U1") (pin "P1") (pinfunction "GND_40_P1") (pintype "passive"))
      (node (ref "U1") (pin "R14") (pinfunction "GND_42_R14") (pintype "passive"))
      (node (ref "U1") (pin "R4") (pinfunction "GND_41_R4") (pintype "passive"))
      (node (ref "U1") (pin "T17") (pinfunction "GND_44_T17") (pintype "passive"))
      (node (ref "U1") (pin "T7") (pinfunction "GND_43_T7") (pintype "passive"))
      (node (ref "U1") (pin "U10") (pinfunction "GND_45_U10") (pintype "passive"))
      (node (ref "U1") (pin "V13") (pinfunction "GND_47_V13") (pintype "passive"))
      (node (ref "U1") (pin "V3") (pinfunction "GND_46_V3") (pintype "passive"))
      (node (ref "U2") (pin "4") (pinfunction "VSS_4") (pintype "power_in"))
      (node (ref "U3") (pin "15") (pinfunction "PGND_15") (pintype "power_in"))
      (node (ref "U3") (pin "16") (pinfunction "PGND_16") (pintype "power_in"))
      (node (ref "U3") (pin "17") (pinfunction "Exposed_Thermal_Pad_17") (pintype "power_in"))
      (node (ref "U3") (pin "6") (pinfunction "AGND_6") (pintype "power_in"))
      (node (ref "U3") (pin "7") (pinfunction "FSW_7") (pintype "input"))
      (node (ref "U3") (pin "8") (pinfunction "DEF_8") (pintype "input"))
      (node (ref "U4") (pin "15") (pinfunction "PGND_15") (pintype "power_in"))
      (node (ref "U4") (pin "16") (pinfunction "PGND_16") (pintype "power_in"))
      (node (ref "U4") (pin "17") (pinfunction "Exposed_Thermal_Pad_17") (pintype "power_in"))
      (node (ref "U4") (pin "6") (pinfunction "AGND_6") (pintype "power_in"))
      (node (ref "U4") (pin "7") (pinfunction "FSW_7") (pintype "input"))
      (node (ref "U4") (pin "8") (pinfunction "DEF_8") (pintype "input"))
      (node (ref "U5") (pin "15") (pinfunction "PGND_15") (pintype "power_in"))
      (node (ref "U5") (pin "16") (pinfunction "PGND_16") (pintype "power_in"))
      (node (ref "U5") (pin "17") (pinfunction "Exposed_Thermal_Pad_17") (pintype "power_in"))
      (node (ref "U5") (pin "6") (pinfunction "AGND_6") (pintype "power_in"))
      (node (ref "U5") (pin "7") (pinfunction "FSW_7") (pintype "input"))
      (node (ref "U5") (pin "8") (pinfunction "DEF_8") (pintype "input"))
      (node (ref "X1") (pin "2") (pinfunction "GND_2") (pintype "power_in"))
    )
    (net (code "48") (name "Net-(U1-DONE_0)") (class "Default")
      (node (ref "R24") (pin "1") (pinfunction "1_1") (pintype "passive"))
      (node (ref "U1") (pin "P10") (pinfunction "DONE_0_P10") (pintype "passive"))
    )
    (net (code "49") (name "Net-(U1-INIT_B_0)") (class "Default")
      (node (ref "R23") (pin "1") (pinfunction "1_1") (pintype "passive"))
      (node (ref "U1") (pin "P7") (pinfunction "INIT_B_0_P7") (pintype "passive"))
    )
    (net (code "50") (name "Net-(U1-M0_0)") (class "Default")
      (node (ref "R19") (pin "1") (pinfunction "1_1") (pintype "passive"))
      (node (ref "U1") (pin "P12") (pinfunction "M0_0_P12") (pintype "passive"))
    )
    (net (code "51") (name "Net-(U1-M1_0)") (class "Default")
      (node (ref "R20") (pin "1") (pinfunction "1_1") (pintype "passive"))
      (node (ref "U1") (pin "P13") (pinfunction "M1_0_P13") (pintype "passive"))
    )
    (net (code "52") (name "Net-(U1-M2_0)") (class "Default")
      (node (ref "R21") (pin "1") (pinfunction "1_1") (pintype "passive"))
      (node (ref "U1") (pin "P11") (pinfunction "M2_0_P11") (pintype "passive"))
    )
    (net (code "53") (name "Net-(U1-PROGRAM_B_0)") (class "Default")
      (node (ref "R22") (pin "1") (pinfunction "1_1") (pintype "passive"))
      (node (ref "U1") (pin "P9") (pinfunction "PROGRAM_B_0_P9") (pintype "passive"))
    )
    (net (code "54") (name "unconnected-(J2-Pad9)") (class "Default")
      (node (ref "J2") (pin "9") (pinfunction "9_9") (pintype "passive"))
    )
    (net (code "55") (name "unconnected-(U1-DXN_0-PadL9)") (class "Default")
      (node (ref "U1") (pin "L9") (pinfunction "DXN_0_L9") (pintype "passive"))
    )
    (net (code "56") (name "unconnected-(U1-DXP_0-PadL10)") (class "Default")
      (node (ref "U1") (pin "L10") (pinfunction "DXP_0_L10") (pintype "passive"))
    )
    (net (code "57") (name "unconnected-(U1-IO_0_14-PadR11)") (class "Default")
      (node (ref "U1") (pin "R11") (pinfunction "IO_0_14_R11") (pintype "passive"))
    )
    (net (code "58") (name "unconnected-(U1-IO_0_34-PadK6)") (class "Default")
      (node (ref "U1") (pin "K6") (pinfunction "IO_0_34_K6") (pintype "passive"))
    )
    (net (code "59") (name "unconnected-(U1-IO_0_35-PadF5)") (class "Default")
      (node (ref "U1") (pin "F5") (pinfunction "IO_0_35_F5") (pintype "passive"))
    )
    (net (code "60") (name "unconnected-(U1-IO_25_14-PadR10)") (class "Default")
      (node (ref "U1") (pin "R10") (pinfunction "IO_25_14_R10") (pintype "passive"))
    )
    (net (code "61") (name "unconnected-(U1-IO_25_34-PadU8)") (class "Default")
      (node (ref "U1") (pin "U8") (pinfunction "IO_25_34_U8") (pintype "passive"))
    )
    (net (code "62") (name "unconnected-(U1-IO_25_35-PadJ5)") (class "Default")
      (node (ref "U1") (pin "J5") (pinfunction "IO_25_35_J5") (pintype "passive"))
    )
    (net (code "63") (name "unconnected-(U1-IO_L1N_T0_34-PadM1)") (class "Default")
      (node (ref "U1") (pin "M1") (pinfunction "IO_L1N_T0_34_M1") (pintype "passive"))
    )
    (net (code "64") (name "unconnected-(U1-IO_L1N_T0_AD0N_15-PadC14)") (class "Default")
      (node (ref "U1") (pin "C14") (pinfunction "IO_L1N_T0_AD0N_15_C14") (pintype "passive"))
    )
    (net (code "65") (name "unconnected-(U1-IO_L1N_T0_AD4N_35-PadC5)") (class "Default")
      (node (ref "U1") (pin "C5") (pinfunction "IO_L1N_T0_AD4N_35_C5") (pintype "passive"))
    )
    (net (code "66") (name "unconnected-(U1-IO_L1P_T0_34-PadL1)") (class "Default")
      (node (ref "U1") (pin "L1") (pinfunction "IO_L1P_T0_34_L1") (pintype "passive"))
    )
    (net (code "67") (name "unconnected-(U1-IO_L1P_T0_AD0P_15-PadD14)") (class "Default")
      (node (ref "U1") (pin "D14") (pinfunction "IO_L1P_T0_AD0P_15_D14") (pintype "passive"))
    )
    (net (code "68") (name "unconnected-(U1-IO_L1P_T0_AD4P_35-PadC6)") (class "Default")
      (node (ref "U1") (pin "C6") (pinfunction "IO_L1P_T0_AD4P_35_C6") (pintype "passive"))
    )
    (net (code "69") (name "unconnected-(U1-IO_L2N_T0_34-PadL3)") (class "Default")
      (node (ref "U1") (pin "L3") (pinfunction "IO_L2N_T0_34_L3") (pintype "passive"))
    )
    (net (code "70") (name "unconnected-(U1-IO_L2N_T0_AD8N_15-PadB14)") (class "Default")
      (node (ref "U1") (pin "B14") (pinfunction "IO_L2N_T0_AD8N_15_B14") (pintype "passive"))
    )
    (net (code "71") (name "unconnected-(U1-IO_L2N_T0_AD12N_35-PadB6)") (class "Default")
      (node (ref "U1") (pin "B6") (pinfunction "IO_L2N_T0_AD12N_35_B6") (pintype "passive"))
    )
    (net (code "72") (name "unconnected-(U1-IO_L2P_T0_34-PadK3)") (class "Default")
      (node (ref "U1") (pin "K3") (pinfunction "IO_L2P_T0_34_K3") (pintype "passive"))
    )
    (net (code "73") (name "unconnected-(U1-IO_L2P_T0_AD8P_15-PadB13)") (class "Default")
      (node (ref "U1") (pin "B13") (pinfunction "IO_L2P_T0_AD8P_15_B13") (pintype "passive"))
    )
    (net (code "74") (name "unconnected-(U1-IO_L2P_T0_AD12P_35-PadB7)") (class "Default")
      (node (ref "U1") (pin "B7") (pinfunction "IO_L2P_T0_AD12P_35_B7") (pintype "passive"))
    )
    (net (code "75") (name "unconnected-(U1-IO_L3N_T0_DQS_34-PadN1)") (class "Default")
      (node (ref "U1") (pin "N1") (pinfunction "IO_L3N_T0_DQS_34_N1") (pintype "passive"))
    )
    (net (code "76") (name "unconnected-(U1-IO_L3N_T0_DQS_AD1N_15-PadB12)") (class "Default")
      (node (ref "U1") (pin "B12") (pinfunction "IO_L3N_T0_DQS_AD1N_15_B12") (pintype "passive"))
    )
    (net (code "77") (name "unconnected-(U1-IO_L3N_T0_DQS_AD5N_35-PadA5)") (class "Default")
      (node (ref "U1") (pin "A5") (pinfunction "IO_L3N_T0_DQS_AD5N_35_A5") (pintype "passive"))
    )
    (net (code "78") (name "unconnected-(U1-IO_L3N_T0_DQS_EMCCLK_14-PadL16)") (class "Default")
      (node (ref "U1") (pin "L16") (pinfunction "IO_L3N_T0_DQS_EMCCLK_14_L16") (pintype "passive"))
    )
    (net (code "79") (name "unconnected-(U1-IO_L3P_T0_DQS_34-PadN2)") (class "Default")
      (node (ref "U1") (pin "N2") (pinfunction "IO_L3P_T0_DQS_34_N2") (pintype "passive"))
    )
    (net (code "80") (name "unconnected-(U1-IO_L3P_T0_DQS_AD1P_15-PadC12)") (class "Default")
      (node (ref "U1") (pin "C12") (pinfunction "IO_L3P_T0_DQS_AD1P_15_C12") (pintype "passive"))
    )
    (net (code "81") (name "unconnected-(U1-IO_L3P_T0_DQS_AD5P_35-PadA6)") (class "Default")
      (node (ref "U1") (pin "A6") (pinfunction "IO_L3P_T0_DQS_AD5P_35_A6") (pintype "passive"))
    )
    (net (code "82") (name "unconnected-(U1-IO_L3P_T0_DQS_PUDC_B_14-PadL15)") (class "Default")
      (node (ref "U1") (pin "L15") (pinfunction "IO_L3P_T0_DQS_PUDC_B_14_L15") (pintype "passive"))
    )
    (net (code "83") (name "unconnected-(U1-IO_L4N_T0_34-PadM2)") (class "Default")
      (node (ref "U1") (pin "M2") (pinfunction "IO_L4N_T0_34_M2") (pintype "passive"))
    )
    (net (code "84") (name "unconnected-(U1-IO_L4N_T0_35-PadC7)") (class "Default")
      (node (ref "U1") (pin "C7") (pinfunction "IO_L4N_T0_35_C7") (pintype "passive"))
    )
    (net (code "85") (name "unconnected-(U1-IO_L4N_T0_D05_14-PadM18)") (class "Default")
      (node (ref "U1") (pin "M18") (pinfunction "IO_L4N_T0_D05_14_M18") (pintype "passive"))
    )
    (net (code "86") (name "unconnected-(U1-IO_L4P_T0_34-PadM3)") (class "Default")
      (node (ref "U1") (pin "M3") (pinfunction "IO_L4P_T0_34_M3") (pintype "passive"))
    )
    (net (code "87") (name "unconnected-(U1-IO_L4P_T0_35-PadD8)") (class "Default")
      (node (ref "U1") (pin "D8") (pinfunction "IO_L4P_T0_35_D8") (pintype "passive"))
    )
    (net (code "88") (name "unconnected-(U1-IO_L4P_T0_D04_14-PadL18)") (class "Default")
      (node (ref "U1") (pin "L18") (pinfunction "IO_L4P_T0_D04_14_L18") (pintype "passive"))
    )
    (net (code "89") (name "unconnected-(U1-IO_L5N_T0_34-PadL4)") (class "Default")
      (node (ref "U1") (pin "L4") (pinfunction "IO_L5N_T0_34_L4") (pintype "passive"))
    )
    (net (code "90") (name "unconnected-(U1-IO_L5N_T0_AD9N_15-PadF14)") (class "Default")
      (node (ref "U1") (pin "F14") (pinfunction "IO_L5N_T0_AD9N_15_F14") (pintype "passive"))
    )
    (net (code "91") (name "unconnected-(U1-IO_L5N_T0_AD13N_35-PadE5)") (class "Default")
      (node (ref "U1") (pin "E5") (pinfunction "IO_L5N_T0_AD13N_35_E5") (pintype "passive"))
    )
    (net (code "92") (name "unconnected-(U1-IO_L5N_T0_D07_14-PadR13)") (class "Default")
      (node (ref "U1") (pin "R13") (pinfunction "IO_L5N_T0_D07_14_R13") (pintype "passive"))
    )
    (net (code "93") (name "unconnected-(U1-IO_L5P_T0_34-PadK5)") (class "Default")
      (node (ref "U1") (pin "K5") (pinfunction "IO_L5P_T0_34_K5") (pintype "passive"))
    )
    (net (code "94") (name "unconnected-(U1-IO_L5P_T0_AD9P_15-PadF13)") (class "Default")
      (node (ref "U1") (pin "F13") (pinfunction "IO_L5P_T0_AD9P_15_F13") (pintype "passive"))
    )
    (net (code "95") (name "unconnected-(U1-IO_L5P_T0_AD13P_35-PadE6)") (class "Default")
      (node (ref "U1") (pin "E6") (pinfunction "IO_L5P_T0_AD13P_35_E6") (pintype "passive"))
    )
    (net (code "96") (name "unconnected-(U1-IO_L5P_T0_D06_14-PadR12)") (class "Default")
      (node (ref "U1") (pin "R12") (pinfunction "IO_L5P_T0_D06_14_R12") (pintype "passive"))
    )
    (net (code "97") (name "unconnected-(U1-IO_L6N_T0_D08_VREF_14-PadM13)") (class "Default")
      (node (ref "U1") (pin "M13") (pinfunction "IO_L6N_T0_D08_VREF_14_M13") (pintype "passive"))
    )
    (net (code "98") (name "unconnected-(U1-IO_L6N_T0_VREF_15-PadD13)") (class "Default")
      (node (ref "U1") (pin "D13") (pinfunction "IO_L6N_T0_VREF_15_D13") (pintype "passive"))
    )
    (net (code "99") (name "unconnected-(U1-IO_L6N_T0_VREF_16-PadD9)") (class "Default")
      (node (ref "U1") (pin "D9") (pinfunction "IO_L6N_T0_VREF_16_D9") (pintype "passive"))
    )
    (net (code "100") (name "unconnected-(U1-IO_L6N_T0_VREF_34-PadL5)") (class "Default")
      (node (ref "U1") (pin "L5") (pinfunction "IO_L6N_T0_VREF_34_L5") (pintype "passive"))
    )
    (net (code "101") (name "unconnected-(U1-IO_L6N_T0_VREF_35-PadD7)") (class "Default")
      (node (ref "U1") (pin "D7") (pinfunction "IO_L6N_T0_VREF_35_D7") (pintype "passive"))
    )
    (net (code "102") (name "unconnected-(U1-IO_L6P_T0_34-PadL6)") (class "Default")
      (node (ref "U1") (pin "L6") (pinfunction "IO_L6P_T0_34_L6") (pintype "passive"))
    )
    (net (code "103") (name "unconnected-(U1-IO_L6P_T0_35-PadE7)") (class "Default")
      (node (ref "U1") (pin "E7") (pinfunction "IO_L6P_T0_35_E7") (pintype "passive"))
    )
    (net (code "104") (name "unconnected-(U1-IO_L7N_T1_34-PadV1)") (class "Default")
      (node (ref "U1") (pin "V1") (pinfunction "IO_L7N_T1_34_V1") (pintype "passive"))
    )
    (net (code "105") (name "unconnected-(U1-IO_L7N_T1_AD2N_15-PadB17)") (class "Default")
      (node (ref "U1") (pin "B17") (pinfunction "IO_L7N_T1_AD2N_15_B17") (pintype "passive"))
    )
    (net (code "106") (name "unconnected-(U1-IO_L7N_T1_AD6N_35-PadB4)") (class "Default")
      (node (ref "U1") (pin "B4") (pinfunction "IO_L7N_T1_AD6N_35_B4") (pintype "passive"))
    )
    (net (code "107") (name "unconnected-(U1-IO_L7N_T1_D10_14-PadT18)") (class "Default")
      (node (ref "U1") (pin "T18") (pinfunction "IO_L7N_T1_D10_14_T18") (pintype "passive"))
    )
    (net (code "108") (name "unconnected-(U1-IO_L7P_T1_34-PadU1)") (class "Default")
      (node (ref "U1") (pin "U1") (pinfunction "IO_L7P_T1_34_U1") (pintype "passive"))
    )
    (net (code "109") (name "unconnected-(U1-IO_L7P_T1_AD2P_15-PadB16)") (class "Default")
      (node (ref "U1") (pin "B16") (pinfunction "IO_L7P_T1_AD2P_15_B16") (pintype "passive"))
    )
    (net (code "110") (name "unconnected-(U1-IO_L7P_T1_AD6P_35-PadC4)") (class "Default")
      (node (ref "U1") (pin "C4") (pinfunction "IO_L7P_T1_AD6P_35_C4") (pintype "passive"))
    )
    (net (code "111") (name "unconnected-(U1-IO_L7P_T1_D09_14-PadR18)") (class "Default")
      (node (ref "U1") (pin "R18") (pinfunction "IO_L7P_T1_D09_14_R18") (pintype "passive"))
    )
    (net (code "112") (name "unconnected-(U1-IO_L8N_T1_34-PadU3)") (class "Default")
      (node (ref "U1") (pin "U3") (pinfunction "IO_L8N_T1_34_U3") (pintype "passive"))
    )
    (net (code "113") (name "unconnected-(U1-IO_L8N_T1_AD10N_15-PadA16)") (class "Default")
      (node (ref "U1") (pin "A16") (pinfunction "IO_L8N_T1_AD10N_15_A16") (pintype "passive"))
    )
    (net (code "114") (name "unconnected-(U1-IO_L8N_T1_AD14N_35-PadA3)") (class "Default")
      (node (ref "U1") (pin "A3") (pinfunction "IO_L8N_T1_AD14N_35_A3") (pintype "passive"))
    )
    (net (code "115") (name "unconnected-(U1-IO_L8N_T1_D12_14-PadP14)") (class "Default")
      (node (ref "U1") (pin "P14") (pinfunction "IO_L8N_T1_D12_14_P14") (pintype "passive"))
    )
    (net (code "116") (name "unconnected-(U1-IO_L8P_T1_34-PadU4)") (class "Default")
      (node (ref "U1") (pin "U4") (pinfunction "IO_L8P_T1_34_U4") (pintype "passive"))
    )
    (net (code "117") (name "unconnected-(U1-IO_L8P_T1_AD10P_15-PadA15)") (class "Default")
      (node (ref "U1") (pin "A15") (pinfunction "IO_L8P_T1_AD10P_15_A15") (pintype "passive"))
    )
    (net (code "118") (name "unconnected-(U1-IO_L8P_T1_AD14P_35-PadA4)") (class "Default")
      (node (ref "U1") (pin "A4") (pinfunction "IO_L8P_T1_AD14P_35_A4") (pintype "passive"))
    )
    (net (code "119") (name "unconnected-(U1-IO_L8P_T1_D11_14-PadN14)") (class "Default")
      (node (ref "U1") (pin "N14") (pinfunction "IO_L8P_T1_D11_14_N14") (pintype "passive"))
    )
    (net (code "120") (name "unconnected-(U1-IO_L9N_T1_DQS_34-PadV2)") (class "Default")
      (node (ref "U1") (pin "V2") (pinfunction "IO_L9N_T1_DQS_34_V2") (pintype "passive"))
    )
    (net (code "121") (name "unconnected-(U1-IO_L9N_T1_DQS_AD3N_15-PadA14)") (class "Default")
      (node (ref "U1") (pin "A14") (pinfunction "IO_L9N_T1_DQS_AD3N_15_A14") (pintype "passive"))
    )
    (net (code "122") (name "unconnected-(U1-IO_L9N_T1_DQS_AD7N_35-PadA1)") (class "Default")
      (node (ref "U1") (pin "A1") (pinfunction "IO_L9N_T1_DQS_AD7N_35_A1") (pintype "passive"))
    )
    (net (code "123") (name "unconnected-(U1-IO_L9N_T1_DQS_D13_14-PadP18)") (class "Default")
      (node (ref "U1") (pin "P18") (pinfunction "IO_L9N_T1_DQS_D13_14_P18") (pintype "passive"))
    )
    (net (code "124") (name "unconnected-(U1-IO_L9P_T1_DQS_14-PadN17)") (class "Default")
      (node (ref "U1") (pin "N17") (pinfunction "IO_L9P_T1_DQS_14_N17") (pintype "passive"))
    )
    (net (code "125") (name "unconnected-(U1-IO_L9P_T1_DQS_34-PadU2)") (class "Default")
      (node (ref "U1") (pin "U2") (pinfunction "IO_L9P_T1_DQS_34_U2") (pintype "passive"))
    )
    (net (code "126") (name "unconnected-(U1-IO_L9P_T1_DQS_AD3P_15-PadA13)") (class "Default")
      (node (ref "U1") (pin "A13") (pinfunction "IO_L9P_T1_DQS_AD3P_15_A13") (pintype "passive"))
    )
    (net (code "127") (name "unconnected-(U1-IO_L9P_T1_DQS_AD7P_35-PadB1)") (class "Default")
      (node (ref "U1") (pin "B1") (pinfunction "IO_L9P_T1_DQS_AD7P_35_B1") (pintype "passive"))
    )
    (net (code "128") (name "unconnected-(U1-IO_L10N_T1_34-PadV4)") (class "Default")
      (node (ref "U1") (pin "V4") (pinfunction "IO_L10N_T1_34_V4") (pintype "passive"))
    )
    (net (code "129") (name "unconnected-(U1-IO_L10N_T1_AD11N_15-PadA18)") (class "Default")
      (node (ref "U1") (pin "A18") (pinfunction "IO_L10N_T1_AD11N_15_A18") (pintype "passive"))
    )
    (net (code "130") (name "unconnected-(U1-IO_L10N_T1_AD15N_35-PadB2)") (class "Default")
      (node (ref "U1") (pin "B2") (pinfunction "IO_L10N_T1_AD15N_35_B2") (pintype "passive"))
    )
    (net (code "131") (name "unconnected-(U1-IO_L10N_T1_D15_14-PadM17)") (class "Default")
      (node (ref "U1") (pin "M17") (pinfunction "IO_L10N_T1_D15_14_M17") (pintype "passive"))
    )
    (net (code "132") (name "unconnected-(U1-IO_L10P_T1_34-PadV5)") (class "Default")
      (node (ref "U1") (pin "V5") (pinfunction "IO_L10P_T1_34_V5") (pintype "passive"))
    )
    (net (code "133") (name "unconnected-(U1-IO_L10P_T1_AD11P_15-PadB18)") (class "Default")
      (node (ref "U1") (pin "B18") (pinfunction "IO_L10P_T1_AD11P_15_B18") (pintype "passive"))
    )
    (net (code "134") (name "unconnected-(U1-IO_L10P_T1_AD15P_35-PadB3)") (class "Default")
      (node (ref "U1") (pin "B3") (pinfunction "IO_L10P_T1_AD15P_35_B3") (pintype "passive"))
    )
    (net (code "135") (name "unconnected-(U1-IO_L10P_T1_D14_14-PadM16)") (class "Default")
      (node (ref "U1") (pin "M16") (pinfunction "IO_L10P_T1_D14_14_M16") (pintype "passive"))
    )
    (net (code "136") (name "unconnected-(U1-IO_L11N_T1_SRCC_14-PadN16)") (class "Default")
      (node (ref "U1") (pin "N16") (pinfunction "IO_L11N_T1_SRCC_14_N16") (pintype "passive"))
    )
    (net (code "137") (name "unconnected-(U1-IO_L11N_T1_SRCC_16-PadB9)") (class "Default")
      (node (ref "U1") (pin "B9") (pinfunction "IO_L11N_T1_SRCC_16_B9") (pintype "passive"))
    )
    (net (code "138") (name "unconnected-(U1-IO_L11N_T1_SRCC_34-PadT3)") (class "Default")
      (node (ref "U1") (pin "T3") (pinfunction "IO_L11N_T1_SRCC_34_T3") (pintype "passive"))
    )
    (net (code "139") (name "unconnected-(U1-IO_L11N_T1_SRCC_35-PadD4)") (class "Default")
      (node (ref "U1") (pin "D4") (pinfunction "IO_L11N_T1_SRCC_35_D4") (pintype "passive"))
    )
    (net (code "140") (name "unconnected-(U1-IO_L11P_T1_SRCC_14-PadN15)") (class "Default")
      (node (ref "U1") (pin "N15") (pinfunction "IO_L11P_T1_SRCC_14_N15") (pintype "passive"))
    )
    (net (code "141") (name "unconnected-(U1-IO_L11P_T1_SRCC_16-PadC9)") (class "Default")
      (node (ref "U1") (pin "C9") (pinfunction "IO_L11P_T1_SRCC_16_C9") (pintype "passive"))
    )
    (net (code "142") (name "unconnected-(U1-IO_L11P_T1_SRCC_34-PadR3)") (class "Default")
      (node (ref "U1") (pin "R3") (pinfunction "IO_L11P_T1_SRCC_34_R3") (pintype "passive"))
    )
    (net (code "143") (name "unconnected-(U1-IO_L11P_T1_SRCC_35-PadD5)") (class "Default")
      (node (ref "U1") (pin "D5") (pinfunction "IO_L11P_T1_SRCC_35_D5") (pintype "passive"))
    )
    (net (code "144") (name "unconnected-(U1-IO_L12N_T1_MRCC_14-PadR17)") (class "Default")
      (node (ref "U1") (pin "R17") (pinfunction "IO_L12N_T1_MRCC_14_R17") (pintype "passive"))
    )
    (net (code "145") (name "unconnected-(U1-IO_L12N_T1_MRCC_16-PadA8)") (class "Default")
      (node (ref "U1") (pin "A8") (pinfunction "IO_L12N_T1_MRCC_16_A8") (pintype "passive"))
    )
    (net (code "146") (name "unconnected-(U1-IO_L12N_T1_MRCC_34-PadT4)") (class "Default")
      (node (ref "U1") (pin "T4") (pinfunction "IO_L12N_T1_MRCC_34_T4") (pintype "passive"))
    )
    (net (code "147") (name "unconnected-(U1-IO_L12N_T1_MRCC_35-PadD3)") (class "Default")
      (node (ref "U1") (pin "D3") (pinfunction "IO_L12N_T1_MRCC_35_D3") (pintype "passive"))
    )
    (net (code "148") (name "unconnected-(U1-IO_L12P_T1_MRCC_16-PadB8)") (class "Default")
      (node (ref "U1") (pin "B8") (pinfunction "IO_L12P_T1_MRCC_16_B8") (pintype "passive"))
    )
    (net (code "149") (name "unconnected-(U1-IO_L12P_T1_MRCC_34-PadT5)") (class "Default")
      (node (ref "U1") (pin "T5") (pinfunction "IO_L12P_T1_MRCC_34_T5") (pintype "passive"))
    )
    (net (code "150") (name "unconnected-(U1-IO_L12P_T1_MRCC_35-PadE3)") (class "Default")
      (node (ref "U1") (pin "E3") (pinfunction "IO_L12P_T1_MRCC_35_E3") (pintype "passive"))
    )
    (net (code "151") (name "unconnected-(U1-IO_L13N_T2_MRCC_14-PadR15)") (class "Default")
      (node (ref "U1") (pin "R15") (pinfunction "IO_L13N_T2_MRCC_14_R15") (pintype "passive"))
    )
    (net (code "152") (name "unconnected-(U1-IO_L13N_T2_MRCC_16-PadC10)") (class "Default")
      (node (ref "U1") (pin "C10") (pinfunction "IO_L13N_T2_MRCC_16_C10") (pintype "passive"))
    )
    (net (code "153") (name "unconnected-(U1-IO_L13N_T2_MRCC_34-PadP5)") (class "Default")
      (node (ref "U1") (pin "P5") (pinfunction "IO_L13N_T2_MRCC_34_P5") (pintype "passive"))
    )
    (net (code "154") (name "unconnected-(U1-IO_L13N_T2_MRCC_35-PadF3)") (class "Default")
      (node (ref "U1") (pin "F3") (pinfunction "IO_L13N_T2_MRCC_35_F3") (pintype "passive"))
    )
    (net (code "155") (name "unconnected-(U1-IO_L13P_T2_MRCC_14-PadP15)") (class "Default")
      (node (ref "U1") (pin "P15") (pinfunction "IO_L13P_T2_MRCC_14_P15") (pintype "passive"))
    )
    (net (code "156") (name "unconnected-(U1-IO_L13P_T2_MRCC_16-PadC11)") (class "Default")
      (node (ref "U1") (pin "C11") (pinfunction "IO_L13P_T2_MRCC_16_C11") (pintype "passive"))
    )
    (net (code "157") (name "unconnected-(U1-IO_L13P_T2_MRCC_34-PadN5)") (class "Default")
      (node (ref "U1") (pin "N5") (pinfunction "IO_L13P_T2_MRCC_34_N5") (pintype "passive"))
    )
    (net (code "158") (name "unconnected-(U1-IO_L13P_T2_MRCC_35-PadF4)") (class "Default")
      (node (ref "U1") (pin "F4") (pinfunction "IO_L13P_T2_MRCC_35_F4") (pintype "passive"))
    )
    (net (code "159") (name "unconnected-(U1-IO_L14N_T2_SRCC_14-PadT15)") (class "Default")
      (node (ref "U1") (pin "T15") (pinfunction "IO_L14N_T2_SRCC_14_T15") (pintype "passive"))
    )
    (net (code "160") (name "unconnected-(U1-IO_L14N_T2_SRCC_16-PadA9)") (class "Default")
      (node (ref "U1") (pin "A9") (pinfunction "IO_L14N_T2_SRCC_16_A9") (pintype "passive"))
    )
    (net (code "161") (name "unconnected-(U1-IO_L14N_T2_SRCC_34-PadP3)") (class "Default")
      (node (ref "U1") (pin "P3") (pinfunction "IO_L14N_T2_SRCC_34_P3") (pintype "passive"))
    )
    (net (code "162") (name "unconnected-(U1-IO_L14N_T2_SRCC_35-PadD2)") (class "Default")
      (node (ref "U1") (pin "D2") (pinfunction "IO_L14N_T2_SRCC_35_D2") (pintype "passive"))
    )
    (net (code "163") (name "unconnected-(U1-IO_L14P_T2_SRCC_14-PadT14)") (class "Default")
      (node (ref "U1") (pin "T14") (pinfunction "IO_L14P_T2_SRCC_14_T14") (pintype "passive"))
    )
    (net (code "164") (name "unconnected-(U1-IO_L14P_T2_SRCC_16-PadA10)") (class "Default")
      (node (ref "U1") (pin "A10") (pinfunction "IO_L14P_T2_SRCC_16_A10") (pintype "passive"))
    )
    (net (code "165") (name "unconnected-(U1-IO_L14P_T2_SRCC_34-PadP4)") (class "Default")
      (node (ref "U1") (pin "P4") (pinfunction "IO_L14P_T2_SRCC_34_P4") (pintype "passive"))
    )
    (net (code "166") (name "unconnected-(U1-IO_L14P_T2_SRCC_35-PadE2)") (class "Default")
      (node (ref "U1") (pin "E2") (pinfunction "IO_L14P_T2_SRCC_35_E2") (pintype "passive"))
    )
    (net (code "167") (name "unconnected-(U1-IO_L15N_T2_DQS_34-PadR2)") (class "Default")
      (node (ref "U1") (pin "R2") (pinfunction "IO_L15N_T2_DQS_34_R2") (pintype "passive"))
    )
    (net (code "168") (name "unconnected-(U1-IO_L15N_T2_DQS_35-PadG2)") (class "Default")
      (node (ref "U1") (pin "G2") (pinfunction "IO_L15N_T2_DQS_35_G2") (pintype "passive"))
    )
    (net (code "169") (name "unconnected-(U1-IO_L15N_T2_DQS_ADV_B_15-PadG14)") (class "Default")
      (node (ref "U1") (pin "G14") (pinfunction "IO_L15N_T2_DQS_ADV_B_15_G14") (pintype "passive"))
    )
    (net (code "170") (name "unconnected-(U1-IO_L15N_T2_DQS_DOUT_CSO_B_14-PadT16)") (class "Default")
      (node (ref "U1") (pin "T16") (pinfunction "IO_L15N_T2_DQS_DOUT_CSO_B_14_T16") (pintype "passive"))
    )
    (net (code "171") (name "unconnected-(U1-IO_L15P_T2_DQS_34-PadP2)") (class "Default")
      (node (ref "U1") (pin "P2") (pinfunction "IO_L15P_T2_DQS_34_P2") (pintype "passive"))
    )
    (net (code "172") (name "unconnected-(U1-IO_L15P_T2_DQS_35-PadH2)") (class "Default")
      (node (ref "U1") (pin "H2") (pinfunction "IO_L15P_T2_DQS_35_H2") (pintype "passive"))
    )
    (net (code "173") (name "unconnected-(U1-IO_L15P_T2_DQS_RDWR_B_14-PadR16)") (class "Default")
      (node (ref "U1") (pin "R16") (pinfunction "IO_L15P_T2_DQS_RDWR_B_14_R16") (pintype "passive"))
    )
    (net (code "174") (name "unconnected-(U1-IO_L16N_T2_34-PadN4)") (class "Default")
      (node (ref "U1") (pin "N4") (pinfunction "IO_L16N_T2_34_N4") (pintype "passive"))
    )
    (net (code "175") (name "unconnected-(U1-IO_L16N_T2_35-PadC1)") (class "Default")
      (node (ref "U1") (pin "C1") (pinfunction "IO_L16N_T2_35_C1") (pintype "passive"))
    )
    (net (code "176") (name "unconnected-(U1-IO_L16N_T2_A15_D31_14-PadV16)") (class "Default")
      (node (ref "U1") (pin "V16") (pinfunction "IO_L16N_T2_A15_D31_14_V16") (pintype "passive"))
    )
    (net (code "177") (name "unconnected-(U1-IO_L16N_T2_A27_15-PadD17)") (class "Default")
      (node (ref "U1") (pin "D17") (pinfunction "IO_L16N_T2_A27_15_D17") (pintype "passive"))
    )
    (net (code "178") (name "unconnected-(U1-IO_L16P_T2_34-PadM4)") (class "Default")
      (node (ref "U1") (pin "M4") (pinfunction "IO_L16P_T2_34_M4") (pintype "passive"))
    )
    (net (code "179") (name "unconnected-(U1-IO_L16P_T2_35-PadC2)") (class "Default")
      (node (ref "U1") (pin "C2") (pinfunction "IO_L16P_T2_35_C2") (pintype "passive"))
    )
    (net (code "180") (name "unconnected-(U1-IO_L16P_T2_A28_15-PadE17)") (class "Default")
      (node (ref "U1") (pin "E17") (pinfunction "IO_L16P_T2_A28_15_E17") (pintype "passive"))
    )
    (net (code "181") (name "unconnected-(U1-IO_L16P_T2_CSI_B_14-PadV15)") (class "Default")
      (node (ref "U1") (pin "V15") (pinfunction "IO_L16P_T2_CSI_B_14_V15") (pintype "passive"))
    )
    (net (code "182") (name "unconnected-(U1-IO_L17N_T2_34-PadT1)") (class "Default")
      (node (ref "U1") (pin "T1") (pinfunction "IO_L17N_T2_34_T1") (pintype "passive"))
    )
    (net (code "183") (name "unconnected-(U1-IO_L17N_T2_35-PadG1)") (class "Default")
      (node (ref "U1") (pin "G1") (pinfunction "IO_L17N_T2_35_G1") (pintype "passive"))
    )
    (net (code "184") (name "unconnected-(U1-IO_L17N_T2_A13_D29_14-PadU18)") (class "Default")
      (node (ref "U1") (pin "U18") (pinfunction "IO_L17N_T2_A13_D29_14_U18") (pintype "passive"))
    )
    (net (code "185") (name "unconnected-(U1-IO_L17N_T2_A25_15-PadJ13)") (class "Default")
      (node (ref "U1") (pin "J13") (pinfunction "IO_L17N_T2_A25_15_J13") (pintype "passive"))
    )
    (net (code "186") (name "unconnected-(U1-IO_L17P_T2_34-PadR1)") (class "Default")
      (node (ref "U1") (pin "R1") (pinfunction "IO_L17P_T2_34_R1") (pintype "passive"))
    )
    (net (code "187") (name "unconnected-(U1-IO_L17P_T2_35-PadH1)") (class "Default")
      (node (ref "U1") (pin "H1") (pinfunction "IO_L17P_T2_35_H1") (pintype "passive"))
    )
    (net (code "188") (name "unconnected-(U1-IO_L17P_T2_A14_D30_14-PadU17)") (class "Default")
      (node (ref "U1") (pin "U17") (pinfunction "IO_L17P_T2_A14_D30_14_U17") (pintype "passive"))
    )
    (net (code "189") (name "unconnected-(U1-IO_L17P_T2_A26_15-PadK13)") (class "Default")
      (node (ref "U1") (pin "K13") (pinfunction "IO_L17P_T2_A26_15_K13") (pintype "passive"))
    )
    (net (code "190") (name "unconnected-(U1-IO_L18N_T2_34-PadN6)") (class "Default")
      (node (ref "U1") (pin "N6") (pinfunction "IO_L18N_T2_34_N6") (pintype "passive"))
    )
    (net (code "191") (name "unconnected-(U1-IO_L18N_T2_35-PadE1)") (class "Default")
      (node (ref "U1") (pin "E1") (pinfunction "IO_L18N_T2_35_E1") (pintype "passive"))
    )
    (net (code "192") (name "unconnected-(U1-IO_L18N_T2_A11_D27_14-PadV17)") (class "Default")
      (node (ref "U1") (pin "V17") (pinfunction "IO_L18N_T2_A11_D27_14_V17") (pintype "passive"))
    )
    (net (code "193") (name "unconnected-(U1-IO_L18N_T2_A23_15-PadG17)") (class "Default")
      (node (ref "U1") (pin "G17") (pinfunction "IO_L18N_T2_A23_15_G17") (pintype "passive"))
    )
    (net (code "194") (name "unconnected-(U1-IO_L18P_T2_34-PadM6)") (class "Default")
      (node (ref "U1") (pin "M6") (pinfunction "IO_L18P_T2_34_M6") (pintype "passive"))
    )
    (net (code "195") (name "unconnected-(U1-IO_L18P_T2_35-PadF1)") (class "Default")
      (node (ref "U1") (pin "F1") (pinfunction "IO_L18P_T2_35_F1") (pintype "passive"))
    )
    (net (code "196") (name "unconnected-(U1-IO_L18P_T2_A12_D28_14-PadU16)") (class "Default")
      (node (ref "U1") (pin "U16") (pinfunction "IO_L18P_T2_A12_D28_14_U16") (pintype "passive"))
    )
    (net (code "197") (name "unconnected-(U1-IO_L18P_T2_A24_15-PadH17)") (class "Default")
      (node (ref "U1") (pin "H17") (pinfunction "IO_L18P_T2_A24_15_H17") (pintype "passive"))
    )
    (net (code "198") (name "unconnected-(U1-IO_L19N_T3_A09_D25_VREF_14-PadU11)") (class "Default")
      (node (ref "U1") (pin "U11") (pinfunction "IO_L19N_T3_A09_D25_VREF_14_U11") (pintype "passive"))
    )
    (net (code "199") (name "unconnected-(U1-IO_L19N_T3_A21_VREF_15-PadH15)") (class "Default")
      (node (ref "U1") (pin "H15") (pinfunction "IO_L19N_T3_A21_VREF_15_H15") (pintype "passive"))
    )
    (net (code "200") (name "unconnected-(U1-IO_L19N_T3_VREF_16-PadD10)") (class "Default")
      (node (ref "U1") (pin "D10") (pinfunction "IO_L19N_T3_VREF_16_D10") (pintype "passive"))
    )
    (net (code "201") (name "unconnected-(U1-IO_L19N_T3_VREF_34-PadR5)") (class "Default")
      (node (ref "U1") (pin "R5") (pinfunction "IO_L19N_T3_VREF_34_R5") (pintype "passive"))
    )
    (net (code "202") (name "unconnected-(U1-IO_L19N_T3_VREF_35-PadF6)") (class "Default")
      (node (ref "U1") (pin "F6") (pinfunction "IO_L19N_T3_VREF_35_F6") (pintype "passive"))
    )
    (net (code "203") (name "unconnected-(U1-IO_L19P_T3_34-PadR6)") (class "Default")
      (node (ref "U1") (pin "R6") (pinfunction "IO_L19P_T3_34_R6") (pintype "passive"))
    )
    (net (code "204") (name "unconnected-(U1-IO_L19P_T3_35-PadG6)") (class "Default")
      (node (ref "U1") (pin "G6") (pinfunction "IO_L19P_T3_35_G6") (pintype "passive"))
    )
    (net (code "205") (name "unconnected-(U1-IO_L19P_T3_A10_D26_14-PadT11)") (class "Default")
      (node (ref "U1") (pin "T11") (pinfunction "IO_L19P_T3_A10_D26_14_T11") (pintype "passive"))
    )
    (net (code "206") (name "unconnected-(U1-IO_L19P_T3_A22_15-PadJ14)") (class "Default")
      (node (ref "U1") (pin "J14") (pinfunction "IO_L19P_T3_A22_15_J14") (pintype "passive"))
    )
    (net (code "207") (name "unconnected-(U1-IO_L20N_T3_34-PadV6)") (class "Default")
      (node (ref "U1") (pin "V6") (pinfunction "IO_L20N_T3_34_V6") (pintype "passive"))
    )
    (net (code "208") (name "unconnected-(U1-IO_L20N_T3_35-PadG3)") (class "Default")
      (node (ref "U1") (pin "G3") (pinfunction "IO_L20N_T3_35_G3") (pintype "passive"))
    )
    (net (code "209") (name "unconnected-(U1-IO_L20N_T3_A07_D23_14-PadV12)") (class "Default")
      (node (ref "U1") (pin "V12") (pinfunction "IO_L20N_T3_A07_D23_14_V12") (pintype "passive"))
    )
    (net (code "210") (name "unconnected-(U1-IO_L20N_T3_A19_15-PadC17)") (class "Default")
      (node (ref "U1") (pin "C17") (pinfunction "IO_L20N_T3_A19_15_C17") (pintype "passive"))
    )
    (net (code "211") (name "unconnected-(U1-IO_L20P_T3_34-PadV7)") (class "Default")
      (node (ref "U1") (pin "V7") (pinfunction "IO_L20P_T3_34_V7") (pintype "passive"))
    )
    (net (code "212") (name "unconnected-(U1-IO_L20P_T3_35-PadG4)") (class "Default")
      (node (ref "U1") (pin "G4") (pinfunction "IO_L20P_T3_35_G4") (pintype "passive"))
    )
    (net (code "213") (name "unconnected-(U1-IO_L20P_T3_A08_D24_14-PadU12)") (class "Default")
      (node (ref "U1") (pin "U12") (pinfunction "IO_L20P_T3_A08_D24_14_U12") (pintype "passive"))
    )
    (net (code "214") (name "unconnected-(U1-IO_L20P_T3_A20_15-PadC16)") (class "Default")
      (node (ref "U1") (pin "C16") (pinfunction "IO_L20P_T3_A20_15_C16") (pintype "passive"))
    )
    (net (code "215") (name "unconnected-(U1-IO_L21N_T3_DQS_34-PadV9)") (class "Default")
      (node (ref "U1") (pin "V9") (pinfunction "IO_L21N_T3_DQS_34_V9") (pintype "passive"))
    )
    (net (code "216") (name "unconnected-(U1-IO_L21N_T3_DQS_35-PadH4)") (class "Default")
      (node (ref "U1") (pin "H4") (pinfunction "IO_L21N_T3_DQS_35_H4") (pintype "passive"))
    )
    (net (code "217") (name "unconnected-(U1-IO_L21N_T3_DQS_A06_D22_14-PadV11)") (class "Default")
      (node (ref "U1") (pin "V11") (pinfunction "IO_L21N_T3_DQS_A06_D22_14_V11") (pintype "passive"))
    )
    (net (code "218") (name "unconnected-(U1-IO_L21N_T3_DQS_A18_15-PadD18)") (class "Default")
      (node (ref "U1") (pin "D18") (pinfunction "IO_L21N_T3_DQS_A18_15_D18") (pintype "passive"))
    )
    (net (code "219") (name "unconnected-(U1-IO_L21P_T3_DQS_14-PadV10)") (class "Default")
      (node (ref "U1") (pin "V10") (pinfunction "IO_L21P_T3_DQS_14_V10") (pintype "passive"))
    )
    (net (code "220") (name "unconnected-(U1-IO_L21P_T3_DQS_34-PadU9)") (class "Default")
      (node (ref "U1") (pin "U9") (pinfunction "IO_L21P_T3_DQS_34_U9") (pintype "passive"))
    )
    (net (code "221") (name "unconnected-(U1-IO_L21P_T3_DQS_35-PadJ4)") (class "Default")
      (node (ref "U1") (pin "J4") (pinfunction "IO_L21P_T3_DQS_35_J4") (pintype "passive"))
    )
    (net (code "222") (name "unconnected-(U1-IO_L22N_T3_34-PadU6)") (class "Default")
      (node (ref "U1") (pin "U6") (pinfunction "IO_L22N_T3_34_U6") (pintype "passive"))
    )
    (net (code "223") (name "unconnected-(U1-IO_L22N_T3_35-PadJ2)") (class "Default")
      (node (ref "U1") (pin "J2") (pinfunction "IO_L22N_T3_35_J2") (pintype "passive"))
    )
    (net (code "224") (name "unconnected-(U1-IO_L22N_T3_A04_D20_14-PadV14)") (class "Default")
      (node (ref "U1") (pin "V14") (pinfunction "IO_L22N_T3_A04_D20_14_V14") (pintype "passive"))
    )
    (net (code "225") (name "unconnected-(U1-IO_L22N_T3_A16_15-PadF18)") (class "Default")
      (node (ref "U1") (pin "F18") (pinfunction "IO_L22N_T3_A16_15_F18") (pintype "passive"))
    )
    (net (code "226") (name "unconnected-(U1-IO_L22P_T3_34-PadU7)") (class "Default")
      (node (ref "U1") (pin "U7") (pinfunction "IO_L22P_T3_34_U7") (pintype "passive"))
    )
    (net (code "227") (name "unconnected-(U1-IO_L22P_T3_35-PadJ3)") (class "Default")
      (node (ref "U1") (pin "J3") (pinfunction "IO_L22P_T3_35_J3") (pintype "passive"))
    )
    (net (code "228") (name "unconnected-(U1-IO_L22P_T3_A05_D21_14-PadU14)") (class "Default")
      (node (ref "U1") (pin "U14") (pinfunction "IO_L22P_T3_A05_D21_14_U14") (pintype "passive"))
    )
    (net (code "229") (name "unconnected-(U1-IO_L22P_T3_A17_15-PadG18)") (class "Default")
      (node (ref "U1") (pin "G18") (pinfunction "IO_L22P_T3_A17_15_G18") (pintype "passive"))
    )
    (net (code "230") (name "unconnected-(U1-IO_L23N_T3_34-PadT6)") (class "Default")
      (node (ref "U1") (pin "T6") (pinfunction "IO_L23N_T3_34_T6") (pintype "passive"))
    )
    (net (code "231") (name "unconnected-(U1-IO_L23N_T3_35-PadK1)") (class "Default")
      (node (ref "U1") (pin "K1") (pinfunction "IO_L23N_T3_35_K1") (pintype "passive"))
    )
    (net (code "232") (name "unconnected-(U1-IO_L23N_T3_A02_D18_14-PadU13)") (class "Default")
      (node (ref "U1") (pin "U13") (pinfunction "IO_L23N_T3_A02_D18_14_U13") (pintype "passive"))
    )
    (net (code "233") (name "unconnected-(U1-IO_L23N_T3_FWE_B_15-PadJ18)") (class "Default")
      (node (ref "U1") (pin "J18") (pinfunction "IO_L23N_T3_FWE_B_15_J18") (pintype "passive"))
    )
    (net (code "234") (name "unconnected-(U1-IO_L23P_T3_34-PadR7)") (class "Default")
      (node (ref "U1") (pin "R7") (pinfunction "IO_L23P_T3_34_R7") (pintype "passive"))
    )
    (net (code "235") (name "unconnected-(U1-IO_L23P_T3_35-PadK2)") (class "Default")
      (node (ref "U1") (pin "K2") (pinfunction "IO_L23P_T3_35_K2") (pintype "passive"))
    )
    (net (code "236") (name "unconnected-(U1-IO_L23P_T3_A03_D19_14-PadT13)") (class "Default")
      (node (ref "U1") (pin "T13") (pinfunction "IO_L23P_T3_A03_D19_14_T13") (pintype "passive"))
    )
    (net (code "237") (name "unconnected-(U1-IO_L23P_T3_FOE_B_15-PadJ17)") (class "Default")
      (node (ref "U1") (pin "J17") (pinfunction "IO_L23P_T3_FOE_B_15_J17") (pintype "passive"))
    )
    (net (code "238") (name "unconnected-(U1-IO_L24N_T3_34-PadT8)") (class "Default")
      (node (ref "U1") (pin "T8") (pinfunction "IO_L24N_T3_34_T8") (pintype "passive"))
    )
    (net (code "239") (name "unconnected-(U1-IO_L24N_T3_35-PadH5)") (class "Default")
      (node (ref "U1") (pin "H5") (pinfunction "IO_L24N_T3_35_H5") (pintype "passive"))
    )
    (net (code "240") (name "unconnected-(U1-IO_L24N_T3_A00_D16_14-PadT10)") (class "Default")
      (node (ref "U1") (pin "T10") (pinfunction "IO_L24N_T3_A00_D16_14_T10") (pintype "passive"))
    )
    (net (code "241") (name "unconnected-(U1-IO_L24N_T3_RS0_15-PadJ15)") (class "Default")
      (node (ref "U1") (pin "J15") (pinfunction "IO_L24N_T3_RS0_15_J15") (pintype "passive"))
    )
    (net (code "242") (name "unconnected-(U1-IO_L24P_T3_34-PadR8)") (class "Default")
      (node (ref "U1") (pin "R8") (pinfunction "IO_L24P_T3_34_R8") (pintype "passive"))
    )
    (net (code "243") (name "unconnected-(U1-IO_L24P_T3_35-PadH6)") (class "Default")
      (node (ref "U1") (pin "H6") (pinfunction "IO_L24P_T3_35_H6") (pintype "passive"))
    )
    (net (code "244") (name "unconnected-(U1-IO_L24P_T3_A01_D17_14-PadT9)") (class "Default")
      (node (ref "U1") (pin "T9") (pinfunction "IO_L24P_T3_A01_D17_14_T9") (pintype "passive"))
    )
    (net (code "245") (name "unconnected-(U1-IO_L24P_T3_RS1_15-PadK15)") (class "Default")
      (node (ref "U1") (pin "K15") (pinfunction "IO_L24P_T3_RS1_15_K15") (pintype "passive"))
    )
    (net (code "246") (name "unconnected-(U1-VREFN_0-PadJ9)") (class "Default")
      (node (ref "U1") (pin "J9") (pinfunction "VREFN_0_J9") (pintype "passive"))
    )
    (net (code "247") (name "unconnected-(U1-VREFP_0-PadK10)") (class "Default")
      (node (ref "U1") (pin "K10") (pinfunction "VREFP_0_K10") (pintype "passive"))
    )
  )
)
